# PCB_VHDCI_breakout.net
KiCad netlist of a schematic drawn in Altium Designer
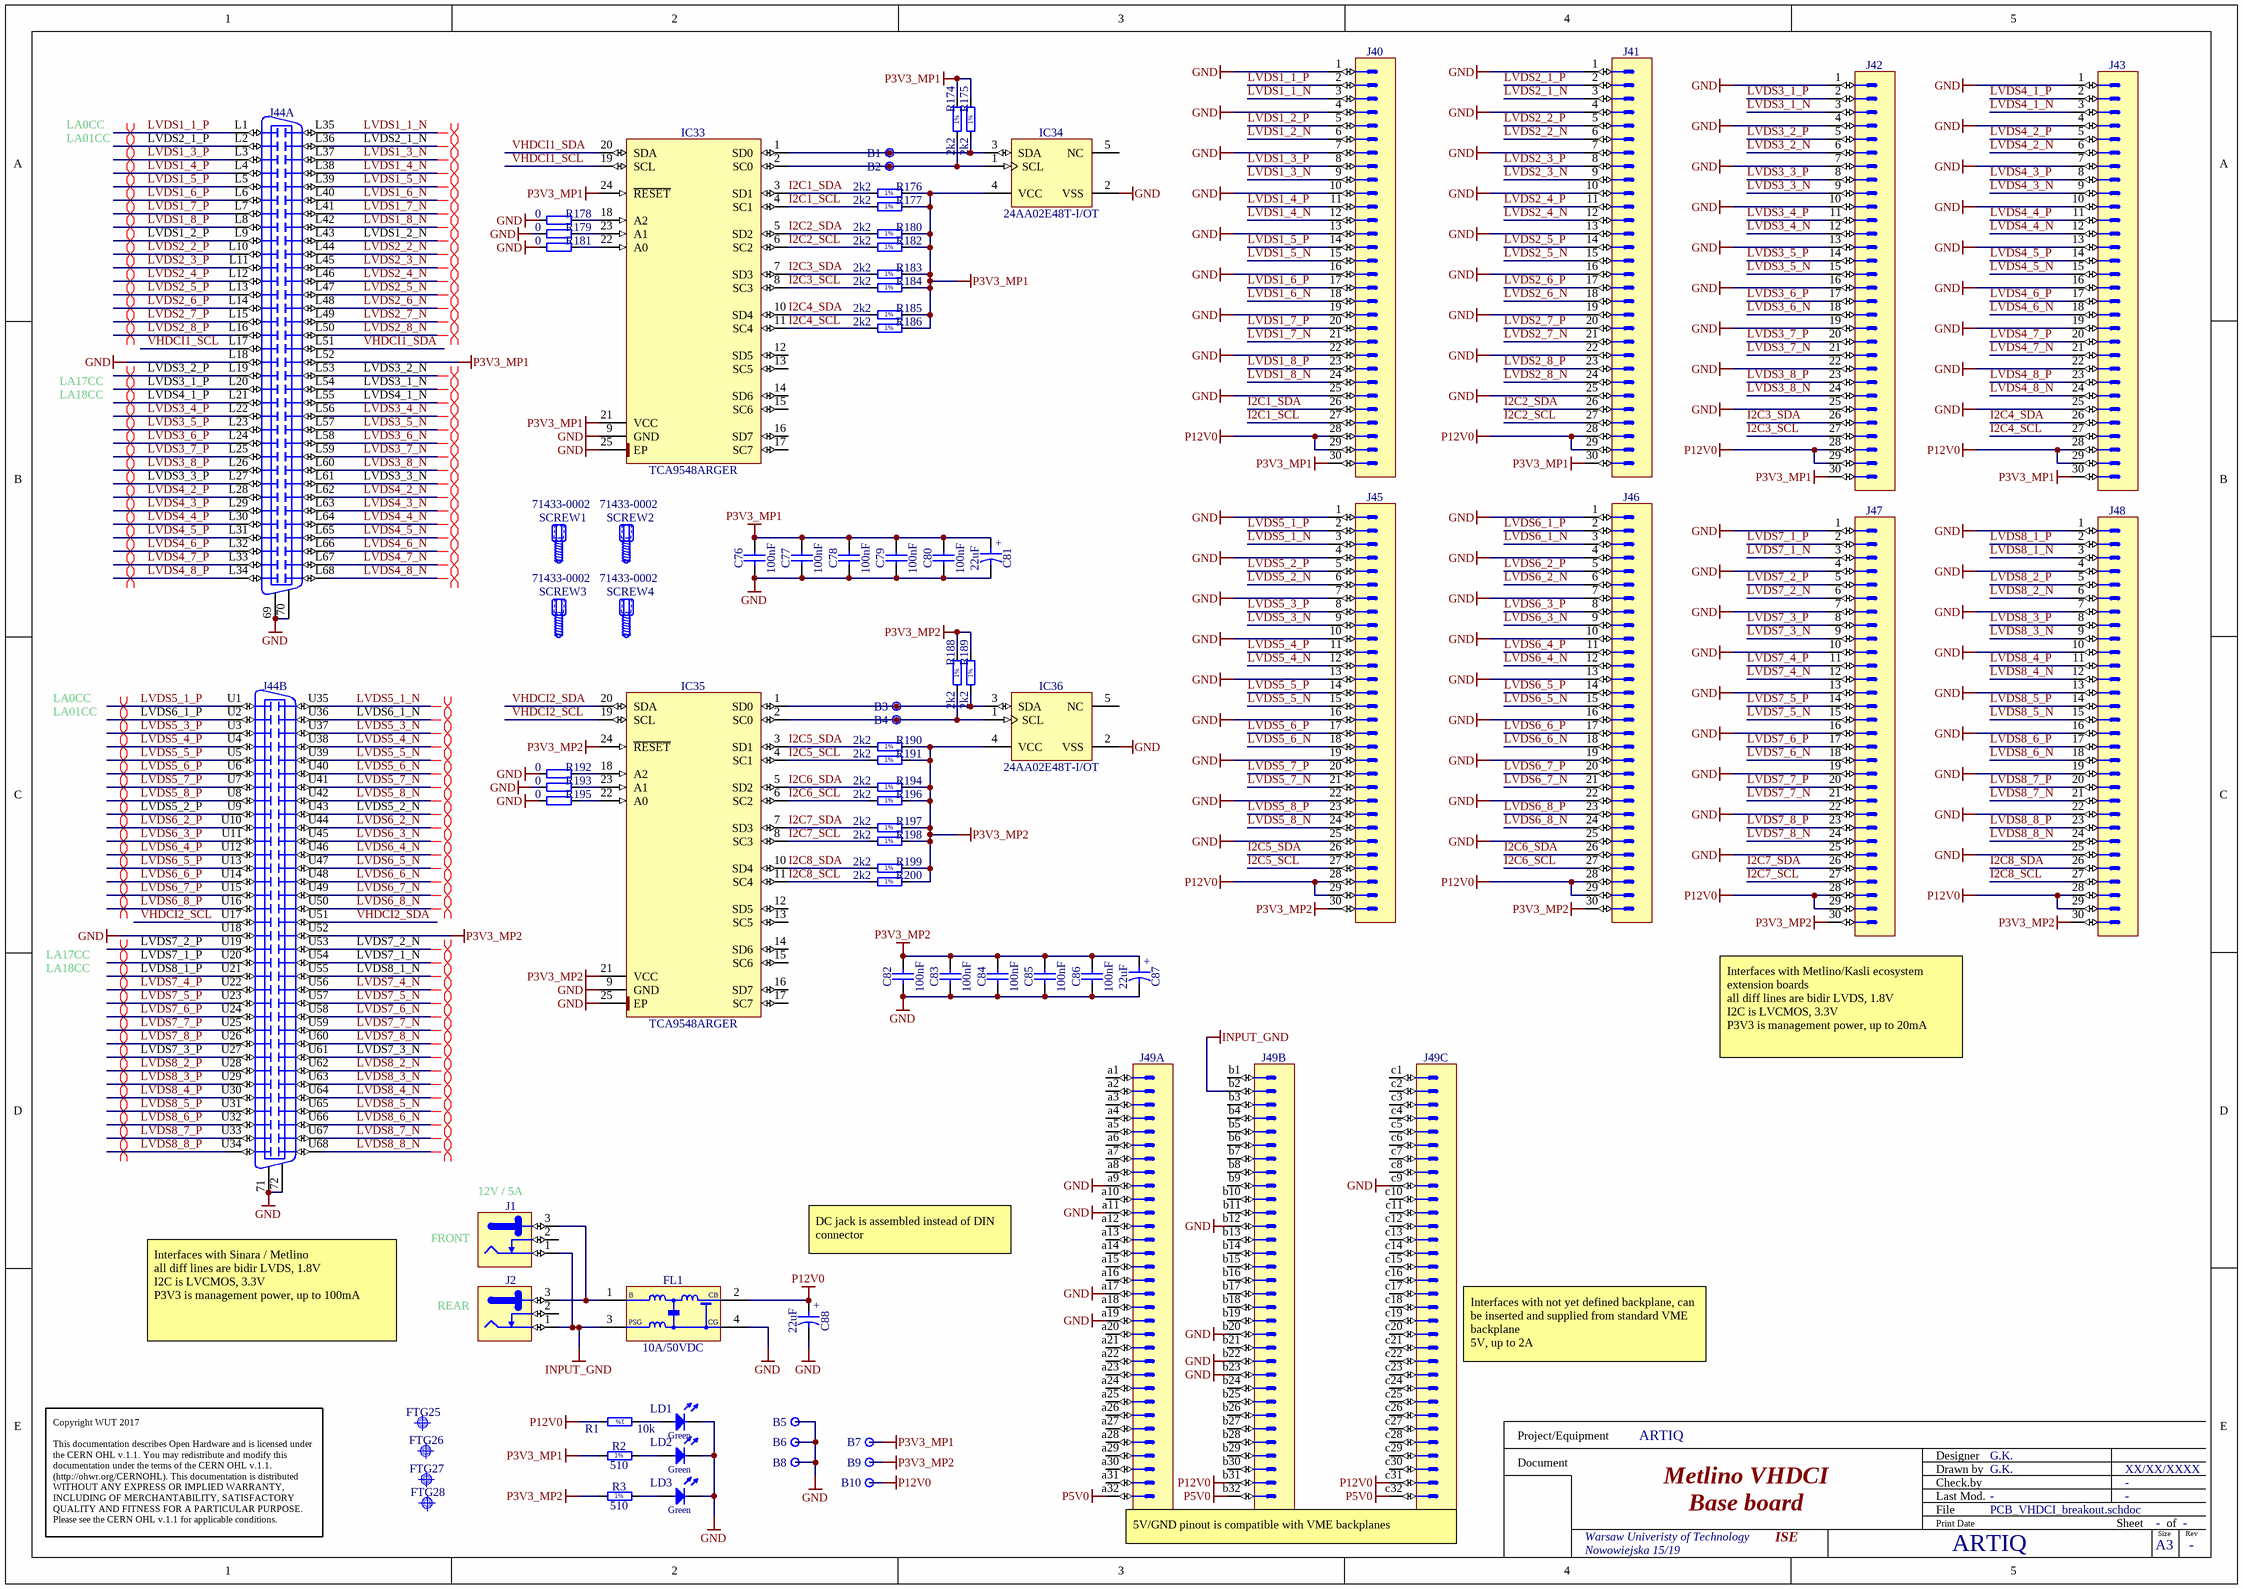
[diagram p0: PCB_VHDCI_breakout.schdoc]

(export (version "E")
  (design (tool "Eeschema 10.0.6"))
  (components
    (comp (ref "B1")
      (value "Plated Hole")
      (footprint "c130h60")
      (description "Single Terminal Socket")
      (fields (field (name "PART NUMBER") "PLATED_HOLE0.6_PAD1.3") (field (name "AUTHOR") "CERN DEM MR"))
      (libsource (lib "Eletro-mechanical") (part "Single Terminal Socket"))
    )
    (comp (ref "B2")
      (value "Plated Hole")
      (footprint "c130h60")
      (description "Single Terminal Socket")
      (fields (field (name "PART NUMBER") "PLATED_HOLE0.6_PAD1.3") (field (name "AUTHOR") "CERN DEM MR"))
      (libsource (lib "Eletro-mechanical") (part "Single Terminal Socket"))
    )
    (comp (ref "B3")
      (value "Plated Hole")
      (footprint "c130h60")
      (description "Single Terminal Socket")
      (fields (field (name "PART NUMBER") "PLATED_HOLE0.6_PAD1.3") (field (name "AUTHOR") "CERN DEM MR"))
      (libsource (lib "Eletro-mechanical") (part "Single Terminal Socket"))
    )
    (comp (ref "B4")
      (value "Plated Hole")
      (footprint "c130h60")
      (description "Single Terminal Socket")
      (fields (field (name "PART NUMBER") "PLATED_HOLE0.6_PAD1.3") (field (name "AUTHOR") "CERN DEM MR"))
      (libsource (lib "Eletro-mechanical") (part "Single Terminal Socket"))
    )
    (comp (ref "B5")
      (value "Plated Hole")
      (footprint "c130h60")
      (description "Single Terminal Socket")
      (fields (field (name "PART NUMBER") "PLATED_HOLE0.6_PAD1.3") (field (name "AUTHOR") "CERN DEM MR"))
      (libsource (lib "Eletro-mechanical") (part "Single Terminal Socket"))
    )
    (comp (ref "B6")
      (value "Plated Hole")
      (footprint "c130h60")
      (description "Single Terminal Socket")
      (fields (field (name "PART NUMBER") "PLATED_HOLE0.6_PAD1.3") (field (name "AUTHOR") "CERN DEM MR"))
      (libsource (lib "Eletro-mechanical") (part "Single Terminal Socket"))
    )
    (comp (ref "B7")
      (value "Plated Hole")
      (footprint "c130h60")
      (description "Single Terminal Socket")
      (fields (field (name "PART NUMBER") "PLATED_HOLE0.6_PAD1.3") (field (name "AUTHOR") "CERN DEM MR"))
      (libsource (lib "Eletro-mechanical") (part "Single Terminal Socket"))
    )
    (comp (ref "B8")
      (value "Plated Hole")
      (footprint "c130h60")
      (description "Single Terminal Socket")
      (fields (field (name "PART NUMBER") "PLATED_HOLE0.6_PAD1.3") (field (name "AUTHOR") "CERN DEM MR"))
      (libsource (lib "Eletro-mechanical") (part "Single Terminal Socket"))
    )
    (comp (ref "B9")
      (value "Plated Hole")
      (footprint "c130h60")
      (description "Single Terminal Socket")
      (fields (field (name "PART NUMBER") "PLATED_HOLE0.6_PAD1.3") (field (name "AUTHOR") "CERN DEM MR"))
      (libsource (lib "Eletro-mechanical") (part "Single Terminal Socket"))
    )
    (comp (ref "B10")
      (value "Plated Hole")
      (footprint "c130h60")
      (description "Single Terminal Socket")
      (fields (field (name "PART NUMBER") "PLATED_HOLE0.6_PAD1.3") (field (name "AUTHOR") "CERN DEM MR"))
      (libsource (lib "Eletro-mechanical") (part "Single Terminal Socket"))
    )
    (comp (ref "C76")
      (value "100nF")
      (footprint "CAPC1005X55N")
      (description "Non-polarised capacitor")
      (fields
        (field (name "PART NUMBER") "CC0402_100NF_16V_10%_X5R")
        (field (name "VOLTAGE") "16V")
        (field (name "AUTHOR") "CERN DEM JLC")
      )
      (libsource (lib "Capacitors") (part "Capacitor - non polarized"))
    )
    (comp (ref "C77")
      (value "100nF")
      (footprint "CAPC1005X55N")
      (description "Non-polarised capacitor")
      (fields
        (field (name "PART NUMBER") "CC0402_100NF_16V_10%_X5R")
        (field (name "VOLTAGE") "16V")
        (field (name "AUTHOR") "CERN DEM JLC")
      )
      (libsource (lib "Capacitors") (part "Capacitor - non polarized"))
    )
    (comp (ref "C78")
      (value "100nF")
      (footprint "CAPC1005X55N")
      (description "Non-polarised capacitor")
      (fields
        (field (name "PART NUMBER") "CC0402_100NF_16V_10%_X5R")
        (field (name "VOLTAGE") "16V")
        (field (name "AUTHOR") "CERN DEM JLC")
      )
      (libsource (lib "Capacitors") (part "Capacitor - non polarized"))
    )
    (comp (ref "C79")
      (value "100nF")
      (footprint "CAPC1005X55N")
      (description "Non-polarised capacitor")
      (fields
        (field (name "PART NUMBER") "CC0402_100NF_16V_10%_X5R")
        (field (name "VOLTAGE") "16V")
        (field (name "AUTHOR") "CERN DEM JLC")
      )
      (libsource (lib "Capacitors") (part "Capacitor - non polarized"))
    )
    (comp (ref "C80")
      (value "100nF")
      (footprint "CAPC1005X55N")
      (description "Non-polarised capacitor")
      (fields
        (field (name "PART NUMBER") "CC0402_100NF_16V_10%_X5R")
        (field (name "VOLTAGE") "16V")
        (field (name "AUTHOR") "CERN DEM JLC")
      )
      (libsource (lib "Capacitors") (part "Capacitor - non polarized"))
    )
    (comp (ref "C81")
      (value "22uF")
      (footprint "CAPAE530X540N")
      (description "Polarised capacitor")
      (fields
        (field (name "PART NUMBER") "CAE530-540_22UF_16V_20%")
        (field (name "VOLTAGE") "16V")
        (field (name "AUTHOR") "CERN DEM JLC")
      )
      (libsource (lib "Capacitors") (part "Capacitor - polarized"))
    )
    (comp (ref "C82")
      (value "100nF")
      (footprint "CAPC1005X55N")
      (description "Non-polarised capacitor")
      (fields
        (field (name "PART NUMBER") "CC0402_100NF_16V_10%_X5R")
        (field (name "VOLTAGE") "16V")
        (field (name "AUTHOR") "CERN DEM JLC")
      )
      (libsource (lib "Capacitors") (part "Capacitor - non polarized"))
    )
    (comp (ref "C83")
      (value "100nF")
      (footprint "CAPC1005X55N")
      (description "Non-polarised capacitor")
      (fields
        (field (name "PART NUMBER") "CC0402_100NF_16V_10%_X5R")
        (field (name "VOLTAGE") "16V")
        (field (name "AUTHOR") "CERN DEM JLC")
      )
      (libsource (lib "Capacitors") (part "Capacitor - non polarized"))
    )
    (comp (ref "C84")
      (value "100nF")
      (footprint "CAPC1005X55N")
      (description "Non-polarised capacitor")
      (fields
        (field (name "PART NUMBER") "CC0402_100NF_16V_10%_X5R")
        (field (name "VOLTAGE") "16V")
        (field (name "AUTHOR") "CERN DEM JLC")
      )
      (libsource (lib "Capacitors") (part "Capacitor - non polarized"))
    )
    (comp (ref "C85")
      (value "100nF")
      (footprint "CAPC1005X55N")
      (description "Non-polarised capacitor")
      (fields
        (field (name "PART NUMBER") "CC0402_100NF_16V_10%_X5R")
        (field (name "VOLTAGE") "16V")
        (field (name "AUTHOR") "CERN DEM JLC")
      )
      (libsource (lib "Capacitors") (part "Capacitor - non polarized"))
    )
    (comp (ref "C86")
      (value "100nF")
      (footprint "CAPC1005X55N")
      (description "Non-polarised capacitor")
      (fields
        (field (name "PART NUMBER") "CC0402_100NF_16V_10%_X5R")
        (field (name "VOLTAGE") "16V")
        (field (name "AUTHOR") "CERN DEM JLC")
      )
      (libsource (lib "Capacitors") (part "Capacitor - non polarized"))
    )
    (comp (ref "C87")
      (value "22uF")
      (footprint "CAPAE530X540N")
      (description "Polarised capacitor")
      (fields
        (field (name "PART NUMBER") "CAE530-540_22UF_16V_20%")
        (field (name "VOLTAGE") "16V")
        (field (name "AUTHOR") "CERN DEM JLC")
      )
      (libsource (lib "Capacitors") (part "Capacitor - polarized"))
    )
    (comp (ref "C88")
      (value "22uF")
      (footprint "CAPAE530X540N")
      (description "Polarised capacitor")
      (fields
        (field (name "PART NUMBER") "CAE530-540_22UF_16V_20%")
        (field (name "VOLTAGE") "16V")
        (field (name "AUTHOR") "CERN DEM JLC")
      )
      (libsource (lib "Capacitors") (part "Capacitor - polarized"))
    )
    (comp (ref "FL1")
      (value "10A/50VDC")
      (footprint "FIL_MURATA_BNX02")
      (description "Block Type EMIFIL (LC Combined)")
      (fields
        (field (name "PART NUMBER") "FIL_MURATA_BNX022-01L")
        (field (name "MANUFACTURER") "MURATA")
        (field (name "AUTHOR") "CERN DEM JLC")
      )
      (libsource (lib "Inductors & Transformers") (part "FIL_MURATA_BNX02"))
    )
    (comp (ref "FTG25")
      (value "Use only in PCB")
      (footprint "FIDUCIAL_TOP_C100-200")
      (description "Fiducial Target")
      (fields (field (name "PART NUMBER") "FIDUCIAL_TARGET_C100-200") (field (name "AUTHOR") "CERN DEM JLC"))
      (libsource (lib "Eletro-mechanical") (part "Fiducial Target"))
    )
    (comp (ref "FTG26")
      (value "Use only in PCB")
      (footprint "FIDUCIAL_TOP_S100-200")
      (description "Fiducial Target")
      (fields (field (name "PART NUMBER") "FIDUCIAL_TARGET_S100-200") (field (name "AUTHOR") "CERN DEM JLC"))
      (libsource (lib "Eletro-mechanical") (part "Fiducial Target"))
    )
    (comp (ref "FTG27")
      (value "Use only in PCB")
      (footprint "FIDUCIAL_TOP_S200-400")
      (description "Fiducial Target")
      (fields (field (name "PART NUMBER") "FIDUCIAL_TARGET_S200-400") (field (name "AUTHOR") "CERN DEM JLC"))
      (libsource (lib "Eletro-mechanical") (part "Fiducial Target"))
    )
    (comp (ref "FTG28")
      (value "Use only in PCB")
      (footprint "FIDUCIAL_TOP_S100-200")
      (description "Fiducial Target")
      (fields (field (name "PART NUMBER") "FIDUCIAL_TARGET_S100-200") (field (name "AUTHOR") "CERN DEM JLC"))
      (libsource (lib "Eletro-mechanical") (part "Fiducial Target"))
    )
    (comp (ref "IC33")
      (value "TCA9548ARGER")
      (footprint "QFN50P400X400X100-25N-S220")
      (description "Low Voltage 8-Channel I2C Switch With Reset")
      (fields (field (name "MANUFACTURER") "TEXAS INSTRUMENTS") (field (name "AUTHOR") "CERN DEM JLC"))
      (libsource (lib "ICs And Semiconductors") (part "TCA9548ARGER"))
    )
    (comp (ref "IC34")
      (value "24AA02E48T-I/OT")
      (footprint "SOT95P280X145-5N")
      (description "1.7V-5.5V, 2K I2C Serial EEPROM With EUI-48 Node Identity")
      (fields (field (name "MANUFACTURER") "MICROCHIP TECHNOLOGY") (field (name "AUTHOR") "CERN DEM MR"))
      (libsource (lib "ICs And Semiconductors") (part "24AA02E48T-I/OT"))
    )
    (comp (ref "IC35")
      (value "TCA9548ARGER")
      (footprint "QFN50P400X400X100-25N-S220")
      (description "Low Voltage 8-Channel I2C Switch With Reset")
      (fields (field (name "MANUFACTURER") "TEXAS INSTRUMENTS") (field (name "AUTHOR") "CERN DEM JLC"))
      (libsource (lib "ICs And Semiconductors") (part "TCA9548ARGER"))
    )
    (comp (ref "IC36")
      (value "24AA02E48T-I/OT")
      (footprint "SOT95P280X145-5N")
      (description "1.7V-5.5V, 2K I2C Serial EEPROM With EUI-48 Node Identity")
      (fields (field (name "MANUFACTURER") "MICROCHIP TECHNOLOGY") (field (name "AUTHOR") "CERN DEM MR"))
      (libsource (lib "ICs And Semiconductors") (part "24AA02E48T-I/OT"))
    )
    (comp (ref "J1")
      (value "Jack")
      (footprint "SWITCHCRAFT_L712RA")
      (description "24V /3. 5A, 2.1mm Diameter Pin, SMD DC Power Supply Connector With  Break Contact")
      (fields
        (field (name "PART NUMBER") "SWITCHCRAFT_L712RA")
        (field (name "MANUFACTURER") "SWITCHCRAFT")
        (field (name "AUTHOR") "GK")
      )
      (libsource (lib "LIBRARY_SCH") (part "CON_DC_5A_THT_RA"))
    )
    (comp (ref "J2")
      (value "Jack")
      (footprint "SWITCHCRAFT_L712RA")
      (description "24V /3. 5A, 2.1mm Diameter Pin, SMD DC Power Supply Connector With  Break Contact")
      (fields
        (field (name "PART NUMBER") "SWITCHCRAFT_L712RA")
        (field (name "MANUFACTURER") "SWITCHCRAFT")
        (field (name "AUTHOR") "GK")
      )
      (libsource (lib "LIBRARY_SCH") (part "CON_DC_5A_THT_RA"))
    )
    (comp (ref "J40")
      (value "~")
      (footprint "3M_N2530-6002RB")
      (description "Connector 30 Male")
      (fields
        (field (name "PART NUMBER") "3M_N2530-6002RB")
        (field (name "MANUFACTURER") "3M")
        (field (name "AUTHOR") "CERN DEM JLC")
      )
      (libsource (lib "Connectors") (part "Connector 30 Male"))
    )
    (comp (ref "J41")
      (value "~")
      (footprint "3M_N2530-6002RB")
      (description "Connector 30 Male")
      (fields
        (field (name "PART NUMBER") "3M_N2530-6002RB")
        (field (name "MANUFACTURER") "3M")
        (field (name "AUTHOR") "CERN DEM JLC")
      )
      (libsource (lib "Connectors") (part "Connector 30 Male"))
    )
    (comp (ref "J42")
      (value "~")
      (footprint "3M_N2530-6002RB")
      (description "Connector 30 Male")
      (fields
        (field (name "PART NUMBER") "3M_N2530-6002RB")
        (field (name "MANUFACTURER") "3M")
        (field (name "AUTHOR") "CERN DEM JLC")
      )
      (libsource (lib "Connectors") (part "Connector 30 Male"))
    )
    (comp (ref "J43")
      (value "~")
      (footprint "3M_N2530-6002RB")
      (description "Connector 30 Male")
      (fields
        (field (name "PART NUMBER") "3M_N2530-6002RB")
        (field (name "MANUFACTURER") "3M")
        (field (name "AUTHOR") "CERN DEM JLC")
      )
      (libsource (lib "Connectors") (part "Connector 30 Male"))
    )
    (comp (ref "J44")
      (value "VHDCI")
      (footprint "MOLEX_74337-0015")
      (description "Very High Density Cable Interconnect (VHDCI ) 2x68 Female")
      (fields
        (field (name "PART NUMBER") "Delivered by GK")
        (field (name "MANUFACTURER") "MOLEX")
        (field (name "AUTHOR") "CERN DEM JLC")
      )
      (libsource (lib "Connectors") (part "Connector VHDCI 2x68 Female"))
    )
    (comp (ref "J45")
      (value "~")
      (footprint "3M_N2530-6002RB")
      (description "Connector 30 Male")
      (fields
        (field (name "PART NUMBER") "3M_N2530-6002RB")
        (field (name "MANUFACTURER") "3M")
        (field (name "AUTHOR") "CERN DEM JLC")
      )
      (libsource (lib "Connectors") (part "Connector 30 Male"))
    )
    (comp (ref "J46")
      (value "~")
      (footprint "3M_N2530-6002RB")
      (description "Connector 30 Male")
      (fields
        (field (name "PART NUMBER") "3M_N2530-6002RB")
        (field (name "MANUFACTURER") "3M")
        (field (name "AUTHOR") "CERN DEM JLC")
      )
      (libsource (lib "Connectors") (part "Connector 30 Male"))
    )
    (comp (ref "J47")
      (value "~")
      (footprint "3M_N2530-6002RB")
      (description "Connector 30 Male")
      (fields
        (field (name "PART NUMBER") "3M_N2530-6002RB")
        (field (name "MANUFACTURER") "3M")
        (field (name "AUTHOR") "CERN DEM JLC")
      )
      (libsource (lib "Connectors") (part "Connector 30 Male"))
    )
    (comp (ref "J48")
      (value "~")
      (footprint "3M_N2530-6002RB")
      (description "Connector 30 Male")
      (fields
        (field (name "PART NUMBER") "3M_N2530-6002RB")
        (field (name "MANUFACTURER") "3M")
        (field (name "AUTHOR") "CERN DEM JLC")
      )
      (libsource (lib "Connectors") (part "Connector 30 Male"))
    )
    (comp (ref "J49")
      (value "DNP")
      (footprint "HARTING_09 03 196 2921")
      (description "Connector 96abc male (3x32)")
      (fields
        (field (name "PART NUMBER") "HARTING_09 03 196 2921")
        (field (name "MANUFACTURER") "HARTING")
        (field (name "AUTHOR") "CERN DEM JLC")
      )
      (libsource (lib "Connectors") (part "Connector 96abc male (3x32)"))
    )
    (comp (ref "LD1")
      (value "Green")
      (footprint "LED_KINGBRIGHT_KPH-1608CGCK")
      (description "LED Green 1C 2A")
      (fields
        (field (name "PART NUMBER") "LED_KINGBRIGHT_KPH-1608CGCK")
        (field (name "MANUFACTURER") "KINGBRIGHT")
        (field (name "AUTHOR") "CERN DEM JLC")
      )
      (libsource (lib "ICs And Semiconductors") (part "LED Green 1C 2A"))
    )
    (comp (ref "LD2")
      (value "Green")
      (footprint "LED_KINGBRIGHT_KPH-1608CGCK")
      (description "LED Green 1C 2A")
      (fields
        (field (name "PART NUMBER") "LED_KINGBRIGHT_KPH-1608CGCK")
        (field (name "MANUFACTURER") "KINGBRIGHT")
        (field (name "AUTHOR") "CERN DEM JLC")
      )
      (libsource (lib "ICs And Semiconductors") (part "LED Green 1C 2A"))
    )
    (comp (ref "LD3")
      (value "Green")
      (footprint "LED_KINGBRIGHT_KPH-1608CGCK")
      (description "LED Green 1C 2A")
      (fields
        (field (name "PART NUMBER") "LED_KINGBRIGHT_KPH-1608CGCK")
        (field (name "MANUFACTURER") "KINGBRIGHT")
        (field (name "AUTHOR") "CERN DEM JLC")
      )
      (libsource (lib "ICs And Semiconductors") (part "LED Green 1C 2A"))
    )
    (comp (ref "R1")
      (value "10k")
      (footprint "RESC1005X40N")
      (description "Resistor - 1%")
      (fields
        (field (name "PART NUMBER") "R0402_10K_1%_0.0625W_100PPM")
        (field (name "POWER") "0.0625W")
        (field (name "AUTHOR") "CERN DEM JLC")
      )
      (libsource (lib "Resistors") (part "Resistor - 1%"))
    )
    (comp (ref "R2")
      (value "510")
      (footprint "RESC1005X40N")
      (description "Resistor - 1%")
      (fields
        (field (name "PART NUMBER") "R0402_510R_1%_0.0625W_100PPM")
        (field (name "POWER") "0.0625W")
        (field (name "AUTHOR") "CERN DEM JLC")
      )
      (libsource (lib "Resistors") (part "Resistor - 1%"))
    )
    (comp (ref "R3")
      (value "510")
      (footprint "RESC1005X40N")
      (description "Resistor - 1%")
      (fields
        (field (name "PART NUMBER") "R0402_510R_1%_0.0625W_100PPM")
        (field (name "POWER") "0.0625W")
        (field (name "AUTHOR") "CERN DEM JLC")
      )
      (libsource (lib "Resistors") (part "Resistor - 1%"))
    )
    (comp (ref "R174")
      (value "2k2")
      (footprint "RESC1005X40N")
      (description "Resistor - 1%")
      (fields
        (field (name "PART NUMBER") "R0402_2K2_1%_0.0625W_100PPM")
        (field (name "POWER") "0.0625W")
        (field (name "AUTHOR") "CERN DEM JLC")
      )
      (libsource (lib "Resistors") (part "Resistor - 1%"))
    )
    (comp (ref "R175")
      (value "2k2")
      (footprint "RESC1005X40N")
      (description "Resistor - 1%")
      (fields
        (field (name "PART NUMBER") "R0402_2K2_1%_0.0625W_100PPM")
        (field (name "POWER") "0.0625W")
        (field (name "AUTHOR") "CERN DEM JLC")
      )
      (libsource (lib "Resistors") (part "Resistor - 1%"))
    )
    (comp (ref "R176")
      (value "2k2")
      (footprint "RESC1005X40N")
      (description "Resistor - 1%")
      (fields
        (field (name "PART NUMBER") "R0402_2K2_1%_0.0625W_100PPM")
        (field (name "POWER") "0.0625W")
        (field (name "AUTHOR") "CERN DEM JLC")
      )
      (libsource (lib "Resistors") (part "Resistor - 1%"))
    )
    (comp (ref "R177")
      (value "2k2")
      (footprint "RESC1005X40N")
      (description "Resistor - 1%")
      (fields
        (field (name "PART NUMBER") "R0402_2K2_1%_0.0625W_100PPM")
        (field (name "POWER") "0.0625W")
        (field (name "AUTHOR") "CERN DEM JLC")
      )
      (libsource (lib "Resistors") (part "Resistor - 1%"))
    )
    (comp (ref "R178")
      (value "0")
      (footprint "RESC1005X40N")
      (description "Resistor")
      (fields
        (field (name "PART NUMBER") "R0402_0R_JUMPER")
        (field (name "MANUFACTURER") "GENERIC")
        (field (name "AUTHOR") "CERN DEM JLC")
      )
      (libsource (lib "Resistors") (part "Resistor"))
    )
    (comp (ref "R179")
      (value "0")
      (footprint "RESC1005X40N")
      (description "Resistor")
      (fields
        (field (name "PART NUMBER") "R0402_0R_JUMPER")
        (field (name "MANUFACTURER") "GENERIC")
        (field (name "AUTHOR") "CERN DEM JLC")
      )
      (libsource (lib "Resistors") (part "Resistor"))
    )
    (comp (ref "R180")
      (value "2k2")
      (footprint "RESC1005X40N")
      (description "Resistor - 1%")
      (fields
        (field (name "PART NUMBER") "R0402_2K2_1%_0.0625W_100PPM")
        (field (name "POWER") "0.0625W")
        (field (name "AUTHOR") "CERN DEM JLC")
      )
      (libsource (lib "Resistors") (part "Resistor - 1%"))
    )
    (comp (ref "R181")
      (value "0")
      (footprint "RESC1005X40N")
      (description "Resistor")
      (fields
        (field (name "PART NUMBER") "R0402_0R_JUMPER")
        (field (name "MANUFACTURER") "GENERIC")
        (field (name "AUTHOR") "CERN DEM JLC")
      )
      (libsource (lib "Resistors") (part "Resistor"))
    )
    (comp (ref "R182")
      (value "2k2")
      (footprint "RESC1005X40N")
      (description "Resistor - 1%")
      (fields
        (field (name "PART NUMBER") "R0402_2K2_1%_0.0625W_100PPM")
        (field (name "POWER") "0.0625W")
        (field (name "AUTHOR") "CERN DEM JLC")
      )
      (libsource (lib "Resistors") (part "Resistor - 1%"))
    )
    (comp (ref "R183")
      (value "2k2")
      (footprint "RESC1005X40N")
      (description "Resistor - 1%")
      (fields
        (field (name "PART NUMBER") "R0402_2K2_1%_0.0625W_100PPM")
        (field (name "POWER") "0.0625W")
        (field (name "AUTHOR") "CERN DEM JLC")
      )
      (libsource (lib "Resistors") (part "Resistor - 1%"))
    )
    (comp (ref "R184")
      (value "2k2")
      (footprint "RESC1005X40N")
      (description "Resistor - 1%")
      (fields
        (field (name "PART NUMBER") "R0402_2K2_1%_0.0625W_100PPM")
        (field (name "POWER") "0.0625W")
        (field (name "AUTHOR") "CERN DEM JLC")
      )
      (libsource (lib "Resistors") (part "Resistor - 1%"))
    )
    (comp (ref "R185")
      (value "2k2")
      (footprint "RESC1005X40N")
      (description "Resistor - 1%")
      (fields
        (field (name "PART NUMBER") "R0402_2K2_1%_0.0625W_100PPM")
        (field (name "POWER") "0.0625W")
        (field (name "AUTHOR") "CERN DEM JLC")
      )
      (libsource (lib "Resistors") (part "Resistor - 1%"))
    )
    (comp (ref "R186")
      (value "2k2")
      (footprint "RESC1005X40N")
      (description "Resistor - 1%")
      (fields
        (field (name "PART NUMBER") "R0402_2K2_1%_0.0625W_100PPM")
        (field (name "POWER") "0.0625W")
        (field (name "AUTHOR") "CERN DEM JLC")
      )
      (libsource (lib "Resistors") (part "Resistor - 1%"))
    )
    (comp (ref "R188")
      (value "2k2")
      (footprint "RESC1005X40N")
      (description "Resistor - 1%")
      (fields
        (field (name "PART NUMBER") "R0402_2K2_1%_0.0625W_100PPM")
        (field (name "POWER") "0.0625W")
        (field (name "AUTHOR") "CERN DEM JLC")
      )
      (libsource (lib "Resistors") (part "Resistor - 1%"))
    )
    (comp (ref "R189")
      (value "2k2")
      (footprint "RESC1005X40N")
      (description "Resistor - 1%")
      (fields
        (field (name "PART NUMBER") "R0402_2K2_1%_0.0625W_100PPM")
        (field (name "POWER") "0.0625W")
        (field (name "AUTHOR") "CERN DEM JLC")
      )
      (libsource (lib "Resistors") (part "Resistor - 1%"))
    )
    (comp (ref "R190")
      (value "2k2")
      (footprint "RESC1005X40N")
      (description "Resistor - 1%")
      (fields
        (field (name "PART NUMBER") "R0402_2K2_1%_0.0625W_100PPM")
        (field (name "POWER") "0.0625W")
        (field (name "AUTHOR") "CERN DEM JLC")
      )
      (libsource (lib "Resistors") (part "Resistor - 1%"))
    )
    (comp (ref "R191")
      (value "2k2")
      (footprint "RESC1005X40N")
      (description "Resistor - 1%")
      (fields
        (field (name "PART NUMBER") "R0402_2K2_1%_0.0625W_100PPM")
        (field (name "POWER") "0.0625W")
        (field (name "AUTHOR") "CERN DEM JLC")
      )
      (libsource (lib "Resistors") (part "Resistor - 1%"))
    )
    (comp (ref "R192")
      (value "0")
      (footprint "RESC1005X40N")
      (description "Resistor")
      (fields
        (field (name "PART NUMBER") "R0402_0R_JUMPER")
        (field (name "MANUFACTURER") "GENERIC")
        (field (name "AUTHOR") "CERN DEM JLC")
      )
      (libsource (lib "Resistors") (part "Resistor"))
    )
    (comp (ref "R193")
      (value "0")
      (footprint "RESC1005X40N")
      (description "Resistor")
      (fields
        (field (name "PART NUMBER") "R0402_0R_JUMPER")
        (field (name "MANUFACTURER") "GENERIC")
        (field (name "AUTHOR") "CERN DEM JLC")
      )
      (libsource (lib "Resistors") (part "Resistor"))
    )
    (comp (ref "R194")
      (value "2k2")
      (footprint "RESC1005X40N")
      (description "Resistor - 1%")
      (fields
        (field (name "PART NUMBER") "R0402_2K2_1%_0.0625W_100PPM")
        (field (name "POWER") "0.0625W")
        (field (name "AUTHOR") "CERN DEM JLC")
      )
      (libsource (lib "Resistors") (part "Resistor - 1%"))
    )
    (comp (ref "R195")
      (value "0")
      (footprint "RESC1005X40N")
      (description "Resistor")
      (fields
        (field (name "PART NUMBER") "R0402_0R_JUMPER")
        (field (name "MANUFACTURER") "GENERIC")
        (field (name "AUTHOR") "CERN DEM JLC")
      )
      (libsource (lib "Resistors") (part "Resistor"))
    )
    (comp (ref "R196")
      (value "2k2")
      (footprint "RESC1005X40N")
      (description "Resistor - 1%")
      (fields
        (field (name "PART NUMBER") "R0402_2K2_1%_0.0625W_100PPM")
        (field (name "POWER") "0.0625W")
        (field (name "AUTHOR") "CERN DEM JLC")
      )
      (libsource (lib "Resistors") (part "Resistor - 1%"))
    )
    (comp (ref "R197")
      (value "2k2")
      (footprint "RESC1005X40N")
      (description "Resistor - 1%")
      (fields
        (field (name "PART NUMBER") "R0402_2K2_1%_0.0625W_100PPM")
        (field (name "POWER") "0.0625W")
        (field (name "AUTHOR") "CERN DEM JLC")
      )
      (libsource (lib "Resistors") (part "Resistor - 1%"))
    )
    (comp (ref "R198")
      (value "2k2")
      (footprint "RESC1005X40N")
      (description "Resistor - 1%")
      (fields
        (field (name "PART NUMBER") "R0402_2K2_1%_0.0625W_100PPM")
        (field (name "POWER") "0.0625W")
        (field (name "AUTHOR") "CERN DEM JLC")
      )
      (libsource (lib "Resistors") (part "Resistor - 1%"))
    )
    (comp (ref "R199")
      (value "2k2")
      (footprint "RESC1005X40N")
      (description "Resistor - 1%")
      (fields
        (field (name "PART NUMBER") "R0402_2K2_1%_0.0625W_100PPM")
        (field (name "POWER") "0.0625W")
        (field (name "AUTHOR") "CERN DEM JLC")
      )
      (libsource (lib "Resistors") (part "Resistor - 1%"))
    )
    (comp (ref "R200")
      (value "2k2")
      (footprint "RESC1005X40N")
      (description "Resistor - 1%")
      (fields
        (field (name "PART NUMBER") "R0402_2K2_1%_0.0625W_100PPM")
        (field (name "POWER") "0.0625W")
        (field (name "AUTHOR") "CERN DEM JLC")
      )
      (libsource (lib "Resistors") (part "Resistor - 1%"))
    )
    (comp (ref "SCREW1")
      (value "71433-0002")
      (footprint "MOLEX_71433-0002")
      (description "VHDCI Female Screw Lock")
      (fields
        (field (name "PART NUMBER") "MOLEX_71433-0002")
        (field (name "MANUFACTURER") "Molex")
        (field (name "AUTHOR") "GK")
      )
      (libsource (lib "LIBRARY_SCH") (part "MECH_VHDCI_screw_lock"))
    )
    (comp (ref "SCREW2")
      (value "71433-0002")
      (footprint "MOLEX_71433-0002")
      (description "VHDCI Female Screw Lock")
      (fields
        (field (name "PART NUMBER") "MOLEX_71433-0002")
        (field (name "MANUFACTURER") "Molex")
        (field (name "AUTHOR") "GK")
      )
      (libsource (lib "LIBRARY_SCH") (part "MECH_VHDCI_screw_lock"))
    )
    (comp (ref "SCREW3")
      (value "71433-0002")
      (footprint "MOLEX_71433-0002")
      (description "VHDCI Female Screw Lock")
      (fields
        (field (name "PART NUMBER") "MOLEX_71433-0002")
        (field (name "MANUFACTURER") "Molex")
        (field (name "AUTHOR") "GK")
      )
      (libsource (lib "LIBRARY_SCH") (part "MECH_VHDCI_screw_lock"))
    )
    (comp (ref "SCREW4")
      (value "71433-0002")
      (footprint "MOLEX_71433-0002")
      (description "VHDCI Female Screw Lock")
      (fields
        (field (name "PART NUMBER") "MOLEX_71433-0002")
        (field (name "MANUFACTURER") "Molex")
        (field (name "AUTHOR") "GK")
      )
      (libsource (lib "LIBRARY_SCH") (part "MECH_VHDCI_screw_lock"))
    )
  )
  (nets
    (net (code "1") (name "/I2C1_SCL") (class "Default")
      (node (ref "IC33") (pin "4") (pinfunction "SC1_4") (pintype "bidirectional"))
      (node (ref "J40") (pin "27") (pinfunction "27_27") (pintype "bidirectional"))
      (node (ref "R177") (pin "1") (pinfunction "1_1") (pintype "passive"))
    )
    (net (code "2") (name "/I2C1_SDA") (class "Default")
      (node (ref "IC33") (pin "3") (pinfunction "SD1_3") (pintype "bidirectional"))
      (node (ref "J40") (pin "26") (pinfunction "26_26") (pintype "bidirectional"))
      (node (ref "R176") (pin "1") (pinfunction "1_1") (pintype "passive"))
    )
    (net (code "3") (name "/I2C2_SCL") (class "Default")
      (node (ref "IC33") (pin "6") (pinfunction "SC2_6") (pintype "bidirectional"))
      (node (ref "J41") (pin "27") (pinfunction "27_27") (pintype "bidirectional"))
      (node (ref "R182") (pin "1") (pinfunction "1_1") (pintype "passive"))
    )
    (net (code "4") (name "/I2C2_SDA") (class "Default")
      (node (ref "IC33") (pin "5") (pinfunction "SD2_5") (pintype "bidirectional"))
      (node (ref "J41") (pin "26") (pinfunction "26_26") (pintype "bidirectional"))
      (node (ref "R180") (pin "1") (pinfunction "1_1") (pintype "passive"))
    )
    (net (code "5") (name "/I2C3_SCL") (class "Default")
      (node (ref "IC33") (pin "8") (pinfunction "SC3_8") (pintype "bidirectional"))
      (node (ref "J42") (pin "27") (pinfunction "27_27") (pintype "bidirectional"))
      (node (ref "R184") (pin "1") (pinfunction "1_1") (pintype "passive"))
    )
    (net (code "6") (name "/I2C3_SDA") (class "Default")
      (node (ref "IC33") (pin "7") (pinfunction "SD3_7") (pintype "bidirectional"))
      (node (ref "J42") (pin "26") (pinfunction "26_26") (pintype "bidirectional"))
      (node (ref "R183") (pin "1") (pinfunction "1_1") (pintype "passive"))
    )
    (net (code "7") (name "/I2C4_SCL") (class "Default")
      (node (ref "IC33") (pin "11") (pinfunction "SC4_11") (pintype "bidirectional"))
      (node (ref "J43") (pin "27") (pinfunction "27_27") (pintype "bidirectional"))
      (node (ref "R186") (pin "1") (pinfunction "1_1") (pintype "passive"))
    )
    (net (code "8") (name "/I2C4_SDA") (class "Default")
      (node (ref "IC33") (pin "10") (pinfunction "SD4_10") (pintype "bidirectional"))
      (node (ref "J43") (pin "26") (pinfunction "26_26") (pintype "bidirectional"))
      (node (ref "R185") (pin "1") (pinfunction "1_1") (pintype "passive"))
    )
    (net (code "9") (name "/I2C5_SCL") (class "Default")
      (node (ref "IC35") (pin "4") (pinfunction "SC1_4") (pintype "bidirectional"))
      (node (ref "J45") (pin "27") (pinfunction "27_27") (pintype "bidirectional"))
      (node (ref "R191") (pin "1") (pinfunction "1_1") (pintype "passive"))
    )
    (net (code "10") (name "/I2C5_SDA") (class "Default")
      (node (ref "IC35") (pin "3") (pinfunction "SD1_3") (pintype "bidirectional"))
      (node (ref "J45") (pin "26") (pinfunction "26_26") (pintype "bidirectional"))
      (node (ref "R190") (pin "1") (pinfunction "1_1") (pintype "passive"))
    )
    (net (code "11") (name "/I2C6_SCL") (class "Default")
      (node (ref "IC35") (pin "6") (pinfunction "SC2_6") (pintype "bidirectional"))
      (node (ref "J46") (pin "27") (pinfunction "27_27") (pintype "bidirectional"))
      (node (ref "R196") (pin "1") (pinfunction "1_1") (pintype "passive"))
    )
    (net (code "12") (name "/I2C6_SDA") (class "Default")
      (node (ref "IC35") (pin "5") (pinfunction "SD2_5") (pintype "bidirectional"))
      (node (ref "J46") (pin "26") (pinfunction "26_26") (pintype "bidirectional"))
      (node (ref "R194") (pin "1") (pinfunction "1_1") (pintype "passive"))
    )
    (net (code "13") (name "/I2C7_SCL") (class "Default")
      (node (ref "IC35") (pin "8") (pinfunction "SC3_8") (pintype "bidirectional"))
      (node (ref "J47") (pin "27") (pinfunction "27_27") (pintype "bidirectional"))
      (node (ref "R198") (pin "1") (pinfunction "1_1") (pintype "passive"))
    )
    (net (code "14") (name "/I2C7_SDA") (class "Default")
      (node (ref "IC35") (pin "7") (pinfunction "SD3_7") (pintype "bidirectional"))
      (node (ref "J47") (pin "26") (pinfunction "26_26") (pintype "bidirectional"))
      (node (ref "R197") (pin "1") (pinfunction "1_1") (pintype "passive"))
    )
    (net (code "15") (name "/I2C8_SCL") (class "Default")
      (node (ref "IC35") (pin "11") (pinfunction "SC4_11") (pintype "bidirectional"))
      (node (ref "J48") (pin "27") (pinfunction "27_27") (pintype "bidirectional"))
      (node (ref "R200") (pin "1") (pinfunction "1_1") (pintype "passive"))
    )
    (net (code "16") (name "/I2C8_SDA") (class "Default")
      (node (ref "IC35") (pin "10") (pinfunction "SD4_10") (pintype "bidirectional"))
      (node (ref "J48") (pin "26") (pinfunction "26_26") (pintype "bidirectional"))
      (node (ref "R199") (pin "1") (pinfunction "1_1") (pintype "passive"))
    )
    (net (code "17") (name "/LVDS1_1_N") (class "Default")
      (node (ref "J40") (pin "3") (pinfunction "3_3") (pintype "bidirectional"))
      (node (ref "J44") (pin "L35") (pinfunction "35_L35") (pintype "bidirectional"))
    )
    (net (code "18") (name "/LVDS1_1_P") (class "Default")
      (node (ref "J40") (pin "2") (pinfunction "2_2") (pintype "bidirectional"))
      (node (ref "J44") (pin "L1") (pinfunction "1_L1") (pintype "bidirectional"))
    )
    (net (code "19") (name "/LVDS1_2_N") (class "Default")
      (node (ref "J40") (pin "6") (pinfunction "6_6") (pintype "bidirectional"))
      (node (ref "J44") (pin "L43") (pinfunction "43_L43") (pintype "bidirectional"))
    )
    (net (code "20") (name "/LVDS1_2_P") (class "Default")
      (node (ref "J40") (pin "5") (pinfunction "5_5") (pintype "bidirectional"))
      (node (ref "J44") (pin "L9") (pinfunction "9_L9") (pintype "bidirectional"))
    )
    (net (code "21") (name "/LVDS1_3_N") (class "Default")
      (node (ref "J40") (pin "9") (pinfunction "9_9") (pintype "bidirectional"))
      (node (ref "J44") (pin "L37") (pinfunction "37_L37") (pintype "bidirectional"))
    )
    (net (code "22") (name "/LVDS1_3_P") (class "Default")
      (node (ref "J40") (pin "8") (pinfunction "8_8") (pintype "bidirectional"))
      (node (ref "J44") (pin "L3") (pinfunction "3_L3") (pintype "bidirectional"))
    )
    (net (code "23") (name "/LVDS1_4_N") (class "Default")
      (node (ref "J40") (pin "12") (pinfunction "12_12") (pintype "bidirectional"))
      (node (ref "J44") (pin "L38") (pinfunction "38_L38") (pintype "bidirectional"))
    )
    (net (code "24") (name "/LVDS1_4_P") (class "Default")
      (node (ref "J40") (pin "11") (pinfunction "11_11") (pintype "bidirectional"))
      (node (ref "J44") (pin "L4") (pinfunction "4_L4") (pintype "bidirectional"))
    )
    (net (code "25") (name "/LVDS1_5_N") (class "Default")
      (node (ref "J40") (pin "15") (pinfunction "15_15") (pintype "bidirectional"))
      (node (ref "J44") (pin "L39") (pinfunction "39_L39") (pintype "bidirectional"))
    )
    (net (code "26") (name "/LVDS1_5_P") (class "Default")
      (node (ref "J40") (pin "14") (pinfunction "14_14") (pintype "bidirectional"))
      (node (ref "J44") (pin "L5") (pinfunction "5_L5") (pintype "bidirectional"))
    )
    (net (code "27") (name "/LVDS1_6_N") (class "Default")
      (node (ref "J40") (pin "18") (pinfunction "18_18") (pintype "bidirectional"))
      (node (ref "J44") (pin "L40") (pinfunction "40_L40") (pintype "bidirectional"))
    )
    (net (code "28") (name "/LVDS1_6_P") (class "Default")
      (node (ref "J40") (pin "17") (pinfunction "17_17") (pintype "bidirectional"))
      (node (ref "J44") (pin "L6") (pinfunction "6_L6") (pintype "bidirectional"))
    )
    (net (code "29") (name "/LVDS1_7_N") (class "Default")
      (node (ref "J40") (pin "21") (pinfunction "21_21") (pintype "bidirectional"))
      (node (ref "J44") (pin "L41") (pinfunction "41_L41") (pintype "bidirectional"))
    )
    (net (code "30") (name "/LVDS1_7_P") (class "Default")
      (node (ref "J40") (pin "20") (pinfunction "20_20") (pintype "bidirectional"))
      (node (ref "J44") (pin "L7") (pinfunction "7_L7") (pintype "bidirectional"))
    )
    (net (code "31") (name "/LVDS1_8_N") (class "Default")
      (node (ref "J40") (pin "24") (pinfunction "24_24") (pintype "bidirectional"))
      (node (ref "J44") (pin "L42") (pinfunction "42_L42") (pintype "bidirectional"))
    )
    (net (code "32") (name "/LVDS1_8_P") (class "Default")
      (node (ref "J40") (pin "23") (pinfunction "23_23") (pintype "bidirectional"))
      (node (ref "J44") (pin "L8") (pinfunction "8_L8") (pintype "bidirectional"))
    )
    (net (code "33") (name "/LVDS2_1_N") (class "Default")
      (node (ref "J41") (pin "3") (pinfunction "3_3") (pintype "bidirectional"))
      (node (ref "J44") (pin "L36") (pinfunction "36_L36") (pintype "bidirectional"))
    )
    (net (code "34") (name "/LVDS2_1_P") (class "Default")
      (node (ref "J41") (pin "2") (pinfunction "2_2") (pintype "bidirectional"))
      (node (ref "J44") (pin "L2") (pinfunction "2_L2") (pintype "bidirectional"))
    )
    (net (code "35") (name "/LVDS2_2_N") (class "Default")
      (node (ref "J41") (pin "6") (pinfunction "6_6") (pintype "bidirectional"))
      (node (ref "J44") (pin "L44") (pinfunction "44_L44") (pintype "bidirectional"))
    )
    (net (code "36") (name "/LVDS2_2_P") (class "Default")
      (node (ref "J41") (pin "5") (pinfunction "5_5") (pintype "bidirectional"))
      (node (ref "J44") (pin "L10") (pinfunction "10_L10") (pintype "bidirectional"))
    )
    (net (code "37") (name "/LVDS2_3_N") (class "Default")
      (node (ref "J41") (pin "9") (pinfunction "9_9") (pintype "bidirectional"))
      (node (ref "J44") (pin "L45") (pinfunction "45_L45") (pintype "bidirectional"))
    )
    (net (code "38") (name "/LVDS2_3_P") (class "Default")
      (node (ref "J41") (pin "8") (pinfunction "8_8") (pintype "bidirectional"))
      (node (ref "J44") (pin "L11") (pinfunction "11_L11") (pintype "bidirectional"))
    )
    (net (code "39") (name "/LVDS2_4_N") (class "Default")
      (node (ref "J41") (pin "12") (pinfunction "12_12") (pintype "bidirectional"))
      (node (ref "J44") (pin "L46") (pinfunction "46_L46") (pintype "bidirectional"))
    )
    (net (code "40") (name "/LVDS2_4_P") (class "Default")
      (node (ref "J41") (pin "11") (pinfunction "11_11") (pintype "bidirectional"))
      (node (ref "J44") (pin "L12") (pinfunction "12_L12") (pintype "bidirectional"))
    )
    (net (code "41") (name "/LVDS2_5_N") (class "Default")
      (node (ref "J41") (pin "15") (pinfunction "15_15") (pintype "bidirectional"))
      (node (ref "J44") (pin "L47") (pinfunction "47_L47") (pintype "bidirectional"))
    )
    (net (code "42") (name "/LVDS2_5_P") (class "Default")
      (node (ref "J41") (pin "14") (pinfunction "14_14") (pintype "bidirectional"))
      (node (ref "J44") (pin "L13") (pinfunction "13_L13") (pintype "bidirectional"))
    )
    (net (code "43") (name "/LVDS2_6_N") (class "Default")
      (node (ref "J41") (pin "18") (pinfunction "18_18") (pintype "bidirectional"))
      (node (ref "J44") (pin "L48") (pinfunction "48_L48") (pintype "bidirectional"))
    )
    (net (code "44") (name "/LVDS2_6_P") (class "Default")
      (node (ref "J41") (pin "17") (pinfunction "17_17") (pintype "bidirectional"))
      (node (ref "J44") (pin "L14") (pinfunction "14_L14") (pintype "bidirectional"))
    )
    (net (code "45") (name "/LVDS2_7_N") (class "Default")
      (node (ref "J41") (pin "21") (pinfunction "21_21") (pintype "bidirectional"))
      (node (ref "J44") (pin "L49") (pinfunction "49_L49") (pintype "bidirectional"))
    )
    (net (code "46") (name "/LVDS2_7_P") (class "Default")
      (node (ref "J41") (pin "20") (pinfunction "20_20") (pintype "bidirectional"))
      (node (ref "J44") (pin "L15") (pinfunction "15_L15") (pintype "bidirectional"))
    )
    (net (code "47") (name "/LVDS2_8_N") (class "Default")
      (node (ref "J41") (pin "24") (pinfunction "24_24") (pintype "bidirectional"))
      (node (ref "J44") (pin "L50") (pinfunction "50_L50") (pintype "bidirectional"))
    )
    (net (code "48") (name "/LVDS2_8_P") (class "Default")
      (node (ref "J41") (pin "23") (pinfunction "23_23") (pintype "bidirectional"))
      (node (ref "J44") (pin "L16") (pinfunction "16_L16") (pintype "bidirectional"))
    )
    (net (code "49") (name "/LVDS3_1_N") (class "Default")
      (node (ref "J42") (pin "3") (pinfunction "3_3") (pintype "bidirectional"))
      (node (ref "J44") (pin "L54") (pinfunction "54_L54") (pintype "bidirectional"))
    )
    (net (code "50") (name "/LVDS3_1_P") (class "Default")
      (node (ref "J42") (pin "2") (pinfunction "2_2") (pintype "bidirectional"))
      (node (ref "J44") (pin "L20") (pinfunction "20_L20") (pintype "bidirectional"))
    )
    (net (code "51") (name "/LVDS3_2_N") (class "Default")
      (node (ref "J42") (pin "6") (pinfunction "6_6") (pintype "bidirectional"))
      (node (ref "J44") (pin "L53") (pinfunction "53_L53") (pintype "bidirectional"))
    )
    (net (code "52") (name "/LVDS3_2_P") (class "Default")
      (node (ref "J42") (pin "5") (pinfunction "5_5") (pintype "bidirectional"))
      (node (ref "J44") (pin "L19") (pinfunction "19_L19") (pintype "bidirectional"))
    )
    (net (code "53") (name "/LVDS3_3_N") (class "Default")
      (node (ref "J42") (pin "9") (pinfunction "9_9") (pintype "bidirectional"))
      (node (ref "J44") (pin "L61") (pinfunction "61_L61") (pintype "bidirectional"))
    )
    (net (code "54") (name "/LVDS3_3_P") (class "Default")
      (node (ref "J42") (pin "8") (pinfunction "8_8") (pintype "bidirectional"))
      (node (ref "J44") (pin "L27") (pinfunction "27_L27") (pintype "bidirectional"))
    )
    (net (code "55") (name "/LVDS3_4_N") (class "Default")
      (node (ref "J42") (pin "12") (pinfunction "12_12") (pintype "bidirectional"))
      (node (ref "J44") (pin "L56") (pinfunction "56_L56") (pintype "bidirectional"))
    )
    (net (code "56") (name "/LVDS3_4_P") (class "Default")
      (node (ref "J42") (pin "11") (pinfunction "11_11") (pintype "bidirectional"))
      (node (ref "J44") (pin "L22") (pinfunction "22_L22") (pintype "bidirectional"))
    )
    (net (code "57") (name "/LVDS3_5_N") (class "Default")
      (node (ref "J42") (pin "15") (pinfunction "15_15") (pintype "bidirectional"))
      (node (ref "J44") (pin "L57") (pinfunction "57_L57") (pintype "bidirectional"))
    )
    (net (code "58") (name "/LVDS3_5_P") (class "Default")
      (node (ref "J42") (pin "14") (pinfunction "14_14") (pintype "bidirectional"))
      (node (ref "J44") (pin "L23") (pinfunction "23_L23") (pintype "bidirectional"))
    )
    (net (code "59") (name "/LVDS3_6_N") (class "Default")
      (node (ref "J42") (pin "18") (pinfunction "18_18") (pintype "bidirectional"))
      (node (ref "J44") (pin "L58") (pinfunction "58_L58") (pintype "bidirectional"))
    )
    (net (code "60") (name "/LVDS3_6_P") (class "Default")
      (node (ref "J42") (pin "17") (pinfunction "17_17") (pintype "bidirectional"))
      (node (ref "J44") (pin "L24") (pinfunction "24_L24") (pintype "bidirectional"))
    )
    (net (code "61") (name "/LVDS3_7_N") (class "Default")
      (node (ref "J42") (pin "21") (pinfunction "21_21") (pintype "bidirectional"))
      (node (ref "J44") (pin "L59") (pinfunction "59_L59") (pintype "bidirectional"))
    )
    (net (code "62") (name "/LVDS3_7_P") (class "Default")
      (node (ref "J42") (pin "20") (pinfunction "20_20") (pintype "bidirectional"))
      (node (ref "J44") (pin "L25") (pinfunction "25_L25") (pintype "bidirectional"))
    )
    (net (code "63") (name "/LVDS3_8_N") (class "Default")
      (node (ref "J42") (pin "24") (pinfunction "24_24") (pintype "bidirectional"))
      (node (ref "J44") (pin "L60") (pinfunction "60_L60") (pintype "bidirectional"))
    )
    (net (code "64") (name "/LVDS3_8_P") (class "Default")
      (node (ref "J42") (pin "23") (pinfunction "23_23") (pintype "bidirectional"))
      (node (ref "J44") (pin "L26") (pinfunction "26_L26") (pintype "bidirectional"))
    )
    (net (code "65") (name "/LVDS4_1_N") (class "Default")
      (node (ref "J43") (pin "3") (pinfunction "3_3") (pintype "bidirectional"))
      (node (ref "J44") (pin "L55") (pinfunction "55_L55") (pintype "bidirectional"))
    )
    (net (code "66") (name "/LVDS4_1_P") (class "Default")
      (node (ref "J43") (pin "2") (pinfunction "2_2") (pintype "bidirectional"))
      (node (ref "J44") (pin "L21") (pinfunction "21_L21") (pintype "bidirectional"))
    )
    (net (code "67") (name "/LVDS4_2_N") (class "Default")
      (node (ref "J43") (pin "6") (pinfunction "6_6") (pintype "bidirectional"))
      (node (ref "J44") (pin "L62") (pinfunction "62_L62") (pintype "bidirectional"))
    )
    (net (code "68") (name "/LVDS4_2_P") (class "Default")
      (node (ref "J43") (pin "5") (pinfunction "5_5") (pintype "bidirectional"))
      (node (ref "J44") (pin "L28") (pinfunction "28_L28") (pintype "bidirectional"))
    )
    (net (code "69") (name "/LVDS4_3_N") (class "Default")
      (node (ref "J43") (pin "9") (pinfunction "9_9") (pintype "bidirectional"))
      (node (ref "J44") (pin "L63") (pinfunction "63_L63") (pintype "bidirectional"))
    )
    (net (code "70") (name "/LVDS4_3_P") (class "Default")
      (node (ref "J43") (pin "8") (pinfunction "8_8") (pintype "bidirectional"))
      (node (ref "J44") (pin "L29") (pinfunction "29_L29") (pintype "bidirectional"))
    )
    (net (code "71") (name "/LVDS4_4_N") (class "Default")
      (node (ref "J43") (pin "12") (pinfunction "12_12") (pintype "bidirectional"))
      (node (ref "J44") (pin "L64") (pinfunction "64_L64") (pintype "bidirectional"))
    )
    (net (code "72") (name "/LVDS4_4_P") (class "Default")
      (node (ref "J43") (pin "11") (pinfunction "11_11") (pintype "bidirectional"))
      (node (ref "J44") (pin "L30") (pinfunction "30_L30") (pintype "bidirectional"))
    )
    (net (code "73") (name "/LVDS4_5_N") (class "Default")
      (node (ref "J43") (pin "15") (pinfunction "15_15") (pintype "bidirectional"))
      (node (ref "J44") (pin "L65") (pinfunction "65_L65") (pintype "bidirectional"))
    )
    (net (code "74") (name "/LVDS4_5_P") (class "Default")
      (node (ref "J43") (pin "14") (pinfunction "14_14") (pintype "bidirectional"))
      (node (ref "J44") (pin "L31") (pinfunction "31_L31") (pintype "bidirectional"))
    )
    (net (code "75") (name "/LVDS4_6_N") (class "Default")
      (node (ref "J43") (pin "18") (pinfunction "18_18") (pintype "bidirectional"))
      (node (ref "J44") (pin "L66") (pinfunction "66_L66") (pintype "bidirectional"))
    )
    (net (code "76") (name "/LVDS4_6_P") (class "Default")
      (node (ref "J43") (pin "17") (pinfunction "17_17") (pintype "bidirectional"))
      (node (ref "J44") (pin "L32") (pinfunction "32_L32") (pintype "bidirectional"))
    )
    (net (code "77") (name "/LVDS4_7_N") (class "Default")
      (node (ref "J43") (pin "21") (pinfunction "21_21") (pintype "bidirectional"))
      (node (ref "J44") (pin "L67") (pinfunction "67_L67") (pintype "bidirectional"))
    )
    (net (code "78") (name "/LVDS4_7_P") (class "Default")
      (node (ref "J43") (pin "20") (pinfunction "20_20") (pintype "bidirectional"))
      (node (ref "J44") (pin "L33") (pinfunction "33_L33") (pintype "bidirectional"))
    )
    (net (code "79") (name "/LVDS4_8_N") (class "Default")
      (node (ref "J43") (pin "24") (pinfunction "24_24") (pintype "bidirectional"))
      (node (ref "J44") (pin "L68") (pinfunction "68_L68") (pintype "bidirectional"))
    )
    (net (code "80") (name "/LVDS4_8_P") (class "Default")
      (node (ref "J43") (pin "23") (pinfunction "23_23") (pintype "bidirectional"))
      (node (ref "J44") (pin "L34") (pinfunction "34_L34") (pintype "bidirectional"))
    )
    (net (code "81") (name "/LVDS5_1_N") (class "Default")
      (node (ref "J44") (pin "U35") (pinfunction "35_U35") (pintype "bidirectional"))
      (node (ref "J45") (pin "3") (pinfunction "3_3") (pintype "bidirectional"))
    )
    (net (code "82") (name "/LVDS5_1_P") (class "Default")
      (node (ref "J44") (pin "U1") (pinfunction "1_U1") (pintype "bidirectional"))
      (node (ref "J45") (pin "2") (pinfunction "2_2") (pintype "bidirectional"))
    )
    (net (code "83") (name "/LVDS5_2_N") (class "Default")
      (node (ref "J44") (pin "U43") (pinfunction "43_U43") (pintype "bidirectional"))
      (node (ref "J45") (pin "6") (pinfunction "6_6") (pintype "bidirectional"))
    )
    (net (code "84") (name "/LVDS5_2_P") (class "Default")
      (node (ref "J44") (pin "U9") (pinfunction "9_U9") (pintype "bidirectional"))
      (node (ref "J45") (pin "5") (pinfunction "5_5") (pintype "bidirectional"))
    )
    (net (code "85") (name "/LVDS5_3_N") (class "Default")
      (node (ref "J44") (pin "U37") (pinfunction "37_U37") (pintype "bidirectional"))
      (node (ref "J45") (pin "9") (pinfunction "9_9") (pintype "bidirectional"))
    )
    (net (code "86") (name "/LVDS5_3_P") (class "Default")
      (node (ref "J44") (pin "U3") (pinfunction "3_U3") (pintype "bidirectional"))
      (node (ref "J45") (pin "8") (pinfunction "8_8") (pintype "bidirectional"))
    )
    (net (code "87") (name "/LVDS5_4_N") (class "Default")
      (node (ref "J44") (pin "U38") (pinfunction "38_U38") (pintype "bidirectional"))
      (node (ref "J45") (pin "12") (pinfunction "12_12") (pintype "bidirectional"))
    )
    (net (code "88") (name "/LVDS5_4_P") (class "Default")
      (node (ref "J44") (pin "U4") (pinfunction "4_U4") (pintype "bidirectional"))
      (node (ref "J45") (pin "11") (pinfunction "11_11") (pintype "bidirectional"))
    )
    (net (code "89") (name "/LVDS5_5_N") (class "Default")
      (node (ref "J44") (pin "U39") (pinfunction "39_U39") (pintype "bidirectional"))
      (node (ref "J45") (pin "15") (pinfunction "15_15") (pintype "bidirectional"))
    )
    (net (code "90") (name "/LVDS5_5_P") (class "Default")
      (node (ref "J44") (pin "U5") (pinfunction "5_U5") (pintype "bidirectional"))
      (node (ref "J45") (pin "14") (pinfunction "14_14") (pintype "bidirectional"))
    )
    (net (code "91") (name "/LVDS5_6_N") (class "Default")
      (node (ref "J44") (pin "U40") (pinfunction "40_U40") (pintype "bidirectional"))
      (node (ref "J45") (pin "18") (pinfunction "18_18") (pintype "bidirectional"))
    )
    (net (code "92") (name "/LVDS5_6_P") (class "Default")
      (node (ref "J44") (pin "U6") (pinfunction "6_U6") (pintype "bidirectional"))
      (node (ref "J45") (pin "17") (pinfunction "17_17") (pintype "bidirectional"))
    )
    (net (code "93") (name "/LVDS5_7_N") (class "Default")
      (node (ref "J44") (pin "U41") (pinfunction "41_U41") (pintype "bidirectional"))
      (node (ref "J45") (pin "21") (pinfunction "21_21") (pintype "bidirectional"))
    )
    (net (code "94") (name "/LVDS5_7_P") (class "Default")
      (node (ref "J44") (pin "U7") (pinfunction "7_U7") (pintype "bidirectional"))
      (node (ref "J45") (pin "20") (pinfunction "20_20") (pintype "bidirectional"))
    )
    (net (code "95") (name "/LVDS5_8_N") (class "Default")
      (node (ref "J44") (pin "U42") (pinfunction "42_U42") (pintype "bidirectional"))
      (node (ref "J45") (pin "24") (pinfunction "24_24") (pintype "bidirectional"))
    )
    (net (code "96") (name "/LVDS5_8_P") (class "Default")
      (node (ref "J44") (pin "U8") (pinfunction "8_U8") (pintype "bidirectional"))
      (node (ref "J45") (pin "23") (pinfunction "23_23") (pintype "bidirectional"))
    )
    (net (code "97") (name "/LVDS6_1_N") (class "Default")
      (node (ref "J44") (pin "U36") (pinfunction "36_U36") (pintype "bidirectional"))
      (node (ref "J46") (pin "3") (pinfunction "3_3") (pintype "bidirectional"))
    )
    (net (code "98") (name "/LVDS6_1_P") (class "Default")
      (node (ref "J44") (pin "U2") (pinfunction "2_U2") (pintype "bidirectional"))
      (node (ref "J46") (pin "2") (pinfunction "2_2") (pintype "bidirectional"))
    )
    (net (code "99") (name "/LVDS6_2_N") (class "Default")
      (node (ref "J44") (pin "U44") (pinfunction "44_U44") (pintype "bidirectional"))
      (node (ref "J46") (pin "6") (pinfunction "6_6") (pintype "bidirectional"))
    )
    (net (code "100") (name "/LVDS6_2_P") (class "Default")
      (node (ref "J44") (pin "U10") (pinfunction "10_U10") (pintype "bidirectional"))
      (node (ref "J46") (pin "5") (pinfunction "5_5") (pintype "bidirectional"))
    )
    (net (code "101") (name "/LVDS6_3_N") (class "Default")
      (node (ref "J44") (pin "U45") (pinfunction "45_U45") (pintype "bidirectional"))
      (node (ref "J46") (pin "9") (pinfunction "9_9") (pintype "bidirectional"))
    )
    (net (code "102") (name "/LVDS6_3_P") (class "Default")
      (node (ref "J44") (pin "U11") (pinfunction "11_U11") (pintype "bidirectional"))
      (node (ref "J46") (pin "8") (pinfunction "8_8") (pintype "bidirectional"))
    )
    (net (code "103") (name "/LVDS6_4_N") (class "Default")
      (node (ref "J44") (pin "U46") (pinfunction "46_U46") (pintype "bidirectional"))
      (node (ref "J46") (pin "12") (pinfunction "12_12") (pintype "bidirectional"))
    )
    (net (code "104") (name "/LVDS6_4_P") (class "Default")
      (node (ref "J44") (pin "U12") (pinfunction "12_U12") (pintype "bidirectional"))
      (node (ref "J46") (pin "11") (pinfunction "11_11") (pintype "bidirectional"))
    )
    (net (code "105") (name "/LVDS6_5_N") (class "Default")
      (node (ref "J44") (pin "U47") (pinfunction "47_U47") (pintype "bidirectional"))
      (node (ref "J46") (pin "15") (pinfunction "15_15") (pintype "bidirectional"))
    )
    (net (code "106") (name "/LVDS6_5_P") (class "Default")
      (node (ref "J44") (pin "U13") (pinfunction "13_U13") (pintype "bidirectional"))
      (node (ref "J46") (pin "14") (pinfunction "14_14") (pintype "bidirectional"))
    )
    (net (code "107") (name "/LVDS6_6_N") (class "Default")
      (node (ref "J44") (pin "U48") (pinfunction "48_U48") (pintype "bidirectional"))
      (node (ref "J46") (pin "18") (pinfunction "18_18") (pintype "bidirectional"))
    )
    (net (code "108") (name "/LVDS6_6_P") (class "Default")
      (node (ref "J44") (pin "U14") (pinfunction "14_U14") (pintype "bidirectional"))
      (node (ref "J46") (pin "17") (pinfunction "17_17") (pintype "bidirectional"))
    )
    (net (code "109") (name "/LVDS6_7_N") (class "Default")
      (node (ref "J44") (pin "U49") (pinfunction "49_U49") (pintype "bidirectional"))
      (node (ref "J46") (pin "21") (pinfunction "21_21") (pintype "bidirectional"))
    )
    (net (code "110") (name "/LVDS6_7_P") (class "Default")
      (node (ref "J44") (pin "U15") (pinfunction "15_U15") (pintype "bidirectional"))
      (node (ref "J46") (pin "20") (pinfunction "20_20") (pintype "bidirectional"))
    )
    (net (code "111") (name "/LVDS6_8_N") (class "Default")
      (node (ref "J44") (pin "U50") (pinfunction "50_U50") (pintype "bidirectional"))
      (node (ref "J46") (pin "24") (pinfunction "24_24") (pintype "bidirectional"))
    )
    (net (code "112") (name "/LVDS6_8_P") (class "Default")
      (node (ref "J44") (pin "U16") (pinfunction "16_U16") (pintype "bidirectional"))
      (node (ref "J46") (pin "23") (pinfunction "23_23") (pintype "bidirectional"))
    )
    (net (code "113") (name "/LVDS7_1_N") (class "Default")
      (node (ref "J44") (pin "U54") (pinfunction "54_U54") (pintype "bidirectional"))
      (node (ref "J47") (pin "3") (pinfunction "3_3") (pintype "bidirectional"))
    )
    (net (code "114") (name "/LVDS7_1_P") (class "Default")
      (node (ref "J44") (pin "U20") (pinfunction "20_U20") (pintype "bidirectional"))
      (node (ref "J47") (pin "2") (pinfunction "2_2") (pintype "bidirectional"))
    )
    (net (code "115") (name "/LVDS7_2_N") (class "Default")
      (node (ref "J44") (pin "U53") (pinfunction "53_U53") (pintype "bidirectional"))
      (node (ref "J47") (pin "6") (pinfunction "6_6") (pintype "bidirectional"))
    )
    (net (code "116") (name "/LVDS7_2_P") (class "Default")
      (node (ref "J44") (pin "U19") (pinfunction "19_U19") (pintype "bidirectional"))
      (node (ref "J47") (pin "5") (pinfunction "5_5") (pintype "bidirectional"))
    )
    (net (code "117") (name "/LVDS7_3_N") (class "Default")
      (node (ref "J44") (pin "U61") (pinfunction "61_U61") (pintype "bidirectional"))
      (node (ref "J47") (pin "9") (pinfunction "9_9") (pintype "bidirectional"))
    )
    (net (code "118") (name "/LVDS7_3_P") (class "Default")
      (node (ref "J44") (pin "U27") (pinfunction "27_U27") (pintype "bidirectional"))
      (node (ref "J47") (pin "8") (pinfunction "8_8") (pintype "bidirectional"))
    )
    (net (code "119") (name "/LVDS7_4_N") (class "Default")
      (node (ref "J44") (pin "U56") (pinfunction "56_U56") (pintype "bidirectional"))
      (node (ref "J47") (pin "12") (pinfunction "12_12") (pintype "bidirectional"))
    )
    (net (code "120") (name "/LVDS7_4_P") (class "Default")
      (node (ref "J44") (pin "U22") (pinfunction "22_U22") (pintype "bidirectional"))
      (node (ref "J47") (pin "11") (pinfunction "11_11") (pintype "bidirectional"))
    )
    (net (code "121") (name "/LVDS7_5_N") (class "Default")
      (node (ref "J44") (pin "U57") (pinfunction "57_U57") (pintype "bidirectional"))
      (node (ref "J47") (pin "15") (pinfunction "15_15") (pintype "bidirectional"))
    )
    (net (code "122") (name "/LVDS7_5_P") (class "Default")
      (node (ref "J44") (pin "U23") (pinfunction "23_U23") (pintype "bidirectional"))
      (node (ref "J47") (pin "14") (pinfunction "14_14") (pintype "bidirectional"))
    )
    (net (code "123") (name "/LVDS7_6_N") (class "Default")
      (node (ref "J44") (pin "U58") (pinfunction "58_U58") (pintype "bidirectional"))
      (node (ref "J47") (pin "18") (pinfunction "18_18") (pintype "bidirectional"))
    )
    (net (code "124") (name "/LVDS7_6_P") (class "Default")
      (node (ref "J44") (pin "U24") (pinfunction "24_U24") (pintype "bidirectional"))
      (node (ref "J47") (pin "17") (pinfunction "17_17") (pintype "bidirectional"))
    )
    (net (code "125") (name "/LVDS7_7_N") (class "Default")
      (node (ref "J44") (pin "U59") (pinfunction "59_U59") (pintype "bidirectional"))
      (node (ref "J47") (pin "21") (pinfunction "21_21") (pintype "bidirectional"))
    )
    (net (code "126") (name "/LVDS7_7_P") (class "Default")
      (node (ref "J44") (pin "U25") (pinfunction "25_U25") (pintype "bidirectional"))
      (node (ref "J47") (pin "20") (pinfunction "20_20") (pintype "bidirectional"))
    )
    (net (code "127") (name "/LVDS7_8_N") (class "Default")
      (node (ref "J44") (pin "U60") (pinfunction "60_U60") (pintype "bidirectional"))
      (node (ref "J47") (pin "24") (pinfunction "24_24") (pintype "bidirectional"))
    )
    (net (code "128") (name "/LVDS7_8_P") (class "Default")
      (node (ref "J44") (pin "U26") (pinfunction "26_U26") (pintype "bidirectional"))
      (node (ref "J47") (pin "23") (pinfunction "23_23") (pintype "bidirectional"))
    )
    (net (code "129") (name "/LVDS8_1_N") (class "Default")
      (node (ref "J44") (pin "U55") (pinfunction "55_U55") (pintype "bidirectional"))
      (node (ref "J48") (pin "3") (pinfunction "3_3") (pintype "bidirectional"))
    )
    (net (code "130") (name "/LVDS8_1_P") (class "Default")
      (node (ref "J44") (pin "U21") (pinfunction "21_U21") (pintype "bidirectional"))
      (node (ref "J48") (pin "2") (pinfunction "2_2") (pintype "bidirectional"))
    )
    (net (code "131") (name "/LVDS8_2_N") (class "Default")
      (node (ref "J44") (pin "U62") (pinfunction "62_U62") (pintype "bidirectional"))
      (node (ref "J48") (pin "6") (pinfunction "6_6") (pintype "bidirectional"))
    )
    (net (code "132") (name "/LVDS8_2_P") (class "Default")
      (node (ref "J44") (pin "U28") (pinfunction "28_U28") (pintype "bidirectional"))
      (node (ref "J48") (pin "5") (pinfunction "5_5") (pintype "bidirectional"))
    )
    (net (code "133") (name "/LVDS8_3_N") (class "Default")
      (node (ref "J44") (pin "U63") (pinfunction "63_U63") (pintype "bidirectional"))
      (node (ref "J48") (pin "9") (pinfunction "9_9") (pintype "bidirectional"))
    )
    (net (code "134") (name "/LVDS8_3_P") (class "Default")
      (node (ref "J44") (pin "U29") (pinfunction "29_U29") (pintype "bidirectional"))
      (node (ref "J48") (pin "8") (pinfunction "8_8") (pintype "bidirectional"))
    )
    (net (code "135") (name "/LVDS8_4_N") (class "Default")
      (node (ref "J44") (pin "U64") (pinfunction "64_U64") (pintype "bidirectional"))
      (node (ref "J48") (pin "12") (pinfunction "12_12") (pintype "bidirectional"))
    )
    (net (code "136") (name "/LVDS8_4_P") (class "Default")
      (node (ref "J44") (pin "U30") (pinfunction "30_U30") (pintype "bidirectional"))
      (node (ref "J48") (pin "11") (pinfunction "11_11") (pintype "bidirectional"))
    )
    (net (code "137") (name "/LVDS8_5_N") (class "Default")
      (node (ref "J44") (pin "U65") (pinfunction "65_U65") (pintype "bidirectional"))
      (node (ref "J48") (pin "15") (pinfunction "15_15") (pintype "bidirectional"))
    )
    (net (code "138") (name "/LVDS8_5_P") (class "Default")
      (node (ref "J44") (pin "U31") (pinfunction "31_U31") (pintype "bidirectional"))
      (node (ref "J48") (pin "14") (pinfunction "14_14") (pintype "bidirectional"))
    )
    (net (code "139") (name "/LVDS8_6_N") (class "Default")
      (node (ref "J44") (pin "U66") (pinfunction "66_U66") (pintype "bidirectional"))
      (node (ref "J48") (pin "18") (pinfunction "18_18") (pintype "bidirectional"))
    )
    (net (code "140") (name "/LVDS8_6_P") (class "Default")
      (node (ref "J44") (pin "U32") (pinfunction "32_U32") (pintype "bidirectional"))
      (node (ref "J48") (pin "17") (pinfunction "17_17") (pintype "bidirectional"))
    )
    (net (code "141") (name "/LVDS8_7_N") (class "Default")
      (node (ref "J44") (pin "U67") (pinfunction "67_U67") (pintype "bidirectional"))
      (node (ref "J48") (pin "21") (pinfunction "21_21") (pintype "bidirectional"))
    )
    (net (code "142") (name "/LVDS8_7_P") (class "Default")
      (node (ref "J44") (pin "U33") (pinfunction "33_U33") (pintype "bidirectional"))
      (node (ref "J48") (pin "20") (pinfunction "20_20") (pintype "bidirectional"))
    )
    (net (code "143") (name "/LVDS8_8_N") (class "Default")
      (node (ref "J44") (pin "U68") (pinfunction "68_U68") (pintype "bidirectional"))
      (node (ref "J48") (pin "24") (pinfunction "24_24") (pintype "bidirectional"))
    )
    (net (code "144") (name "/LVDS8_8_P") (class "Default")
      (node (ref "J44") (pin "U34") (pinfunction "34_U34") (pintype "bidirectional"))
      (node (ref "J48") (pin "23") (pinfunction "23_23") (pintype "bidirectional"))
    )
    (net (code "145") (name "/VHDCI1_SCL") (class "Default")
      (node (ref "IC33") (pin "19") (pinfunction "SCL_19") (pintype "bidirectional"))
      (node (ref "J44") (pin "L17") (pinfunction "17_L17") (pintype "bidirectional"))
    )
    (net (code "146") (name "/VHDCI1_SDA") (class "Default")
      (node (ref "IC33") (pin "20") (pinfunction "SDA_20") (pintype "bidirectional"))
      (node (ref "J44") (pin "L51") (pinfunction "51_L51") (pintype "bidirectional"))
    )
    (net (code "147") (name "/VHDCI2_SCL") (class "Default")
      (node (ref "IC35") (pin "19") (pinfunction "SCL_19") (pintype "bidirectional"))
      (node (ref "J44") (pin "U17") (pinfunction "17_U17") (pintype "bidirectional"))
    )
    (net (code "148") (name "/VHDCI2_SDA") (class "Default")
      (node (ref "IC35") (pin "20") (pinfunction "SDA_20") (pintype "bidirectional"))
      (node (ref "J44") (pin "U51") (pinfunction "51_U51") (pintype "bidirectional"))
    )
    (net (code "149") (name "GND") (class "Default")
      (node (ref "B5") (pin "1") (pinfunction "1_1") (pintype "bidirectional"))
      (node (ref "B6") (pin "1") (pinfunction "1_1") (pintype "bidirectional"))
      (node (ref "B8") (pin "1") (pinfunction "1_1") (pintype "bidirectional"))
      (node (ref "C76") (pin "1") (pinfunction "1_1") (pintype "passive"))
      (node (ref "C77") (pin "1") (pinfunction "1_1") (pintype "passive"))
      (node (ref "C78") (pin "1") (pinfunction "1_1") (pintype "passive"))
      (node (ref "C79") (pin "1") (pinfunction "1_1") (pintype "passive"))
      (node (ref "C80") (pin "1") (pinfunction "1_1") (pintype "passive"))
      (node (ref "C81") (pin "2") (pinfunction "2_2") (pintype "passive"))
      (node (ref "C82") (pin "1") (pinfunction "1_1") (pintype "passive"))
      (node (ref "C83") (pin "1") (pinfunction "1_1") (pintype "passive"))
      (node (ref "C84") (pin "1") (pinfunction "1_1") (pintype "passive"))
      (node (ref "C85") (pin "1") (pinfunction "1_1") (pintype "passive"))
      (node (ref "C86") (pin "1") (pinfunction "1_1") (pintype "passive"))
      (node (ref "C87") (pin "2") (pinfunction "2_2") (pintype "passive"))
      (node (ref "C88") (pin "2") (pinfunction "2_2") (pintype "passive"))
      (node (ref "FL1") (pin "4") (pinfunction "CG_4") (pintype "passive"))
      (node (ref "IC33") (pin "25") (pinfunction "EP_25") (pintype "power_in"))
      (node (ref "IC33") (pin "9") (pinfunction "GND_9") (pintype "power_in"))
      (node (ref "IC34") (pin "2") (pinfunction "VSS_2") (pintype "power_in"))
      (node (ref "IC35") (pin "25") (pinfunction "EP_25") (pintype "power_in"))
      (node (ref "IC35") (pin "9") (pinfunction "GND_9") (pintype "power_in"))
      (node (ref "IC36") (pin "2") (pinfunction "VSS_2") (pintype "power_in"))
      (node (ref "J40") (pin "1") (pinfunction "1_1") (pintype "bidirectional"))
      (node (ref "J40") (pin "10") (pinfunction "10_10") (pintype "bidirectional"))
      (node (ref "J40") (pin "13") (pinfunction "13_13") (pintype "bidirectional"))
      (node (ref "J40") (pin "16") (pinfunction "16_16") (pintype "bidirectional"))
      (node (ref "J40") (pin "19") (pinfunction "19_19") (pintype "bidirectional"))
      (node (ref "J40") (pin "22") (pinfunction "22_22") (pintype "bidirectional"))
      (node (ref "J40") (pin "25") (pinfunction "25_25") (pintype "bidirectional"))
      (node (ref "J40") (pin "4") (pinfunction "4_4") (pintype "bidirectional"))
      (node (ref "J40") (pin "7") (pinfunction "7_7") (pintype "bidirectional"))
      (node (ref "J41") (pin "1") (pinfunction "1_1") (pintype "bidirectional"))
      (node (ref "J41") (pin "10") (pinfunction "10_10") (pintype "bidirectional"))
      (node (ref "J41") (pin "13") (pinfunction "13_13") (pintype "bidirectional"))
      (node (ref "J41") (pin "16") (pinfunction "16_16") (pintype "bidirectional"))
      (node (ref "J41") (pin "19") (pinfunction "19_19") (pintype "bidirectional"))
      (node (ref "J41") (pin "22") (pinfunction "22_22") (pintype "bidirectional"))
      (node (ref "J41") (pin "25") (pinfunction "25_25") (pintype "bidirectional"))
      (node (ref "J41") (pin "4") (pinfunction "4_4") (pintype "bidirectional"))
      (node (ref "J41") (pin "7") (pinfunction "7_7") (pintype "bidirectional"))
      (node (ref "J42") (pin "1") (pinfunction "1_1") (pintype "bidirectional"))
      (node (ref "J42") (pin "10") (pinfunction "10_10") (pintype "bidirectional"))
      (node (ref "J42") (pin "13") (pinfunction "13_13") (pintype "bidirectional"))
      (node (ref "J42") (pin "16") (pinfunction "16_16") (pintype "bidirectional"))
      (node (ref "J42") (pin "19") (pinfunction "19_19") (pintype "bidirectional"))
      (node (ref "J42") (pin "22") (pinfunction "22_22") (pintype "bidirectional"))
      (node (ref "J42") (pin "25") (pinfunction "25_25") (pintype "bidirectional"))
      (node (ref "J42") (pin "4") (pinfunction "4_4") (pintype "bidirectional"))
      (node (ref "J42") (pin "7") (pinfunction "7_7") (pintype "bidirectional"))
      (node (ref "J43") (pin "1") (pinfunction "1_1") (pintype "bidirectional"))
      (node (ref "J43") (pin "10") (pinfunction "10_10") (pintype "bidirectional"))
      (node (ref "J43") (pin "13") (pinfunction "13_13") (pintype "bidirectional"))
      (node (ref "J43") (pin "16") (pinfunction "16_16") (pintype "bidirectional"))
      (node (ref "J43") (pin "19") (pinfunction "19_19") (pintype "bidirectional"))
      (node (ref "J43") (pin "22") (pinfunction "22_22") (pintype "bidirectional"))
      (node (ref "J43") (pin "25") (pinfunction "25_25") (pintype "bidirectional"))
      (node (ref "J43") (pin "4") (pinfunction "4_4") (pintype "bidirectional"))
      (node (ref "J43") (pin "7") (pinfunction "7_7") (pintype "bidirectional"))
      (node (ref "J44") (pin "69") (pinfunction "69_69") (pintype "passive"))
      (node (ref "J44") (pin "70") (pinfunction "70_70") (pintype "passive"))
      (node (ref "J44") (pin "71") (pinfunction "71_71") (pintype "passive"))
      (node (ref "J44") (pin "72") (pinfunction "72_72") (pintype "passive"))
      (node (ref "J44") (pin "L18") (pinfunction "18_L18") (pintype "bidirectional"))
      (node (ref "J44") (pin "U18") (pinfunction "18_U18") (pintype "bidirectional"))
      (node (ref "J45") (pin "1") (pinfunction "1_1") (pintype "bidirectional"))
      (node (ref "J45") (pin "10") (pinfunction "10_10") (pintype "bidirectional"))
      (node (ref "J45") (pin "13") (pinfunction "13_13") (pintype "bidirectional"))
      (node (ref "J45") (pin "16") (pinfunction "16_16") (pintype "bidirectional"))
      (node (ref "J45") (pin "19") (pinfunction "19_19") (pintype "bidirectional"))
      (node (ref "J45") (pin "22") (pinfunction "22_22") (pintype "bidirectional"))
      (node (ref "J45") (pin "25") (pinfunction "25_25") (pintype "bidirectional"))
      (node (ref "J45") (pin "4") (pinfunction "4_4") (pintype "bidirectional"))
      (node (ref "J45") (pin "7") (pinfunction "7_7") (pintype "bidirectional"))
      (node (ref "J46") (pin "1") (pinfunction "1_1") (pintype "bidirectional"))
      (node (ref "J46") (pin "10") (pinfunction "10_10") (pintype "bidirectional"))
      (node (ref "J46") (pin "13") (pinfunction "13_13") (pintype "bidirectional"))
      (node (ref "J46") (pin "16") (pinfunction "16_16") (pintype "bidirectional"))
      (node (ref "J46") (pin "19") (pinfunction "19_19") (pintype "bidirectional"))
      (node (ref "J46") (pin "22") (pinfunction "22_22") (pintype "bidirectional"))
      (node (ref "J46") (pin "25") (pinfunction "25_25") (pintype "bidirectional"))
      (node (ref "J46") (pin "4") (pinfunction "4_4") (pintype "bidirectional"))
      (node (ref "J46") (pin "7") (pinfunction "7_7") (pintype "bidirectional"))
      (node (ref "J47") (pin "1") (pinfunction "1_1") (pintype "bidirectional"))
      (node (ref "J47") (pin "10") (pinfunction "10_10") (pintype "bidirectional"))
      (node (ref "J47") (pin "13") (pinfunction "13_13") (pintype "bidirectional"))
      (node (ref "J47") (pin "16") (pinfunction "16_16") (pintype "bidirectional"))
      (node (ref "J47") (pin "19") (pinfunction "19_19") (pintype "bidirectional"))
      (node (ref "J47") (pin "22") (pinfunction "22_22") (pintype "bidirectional"))
      (node (ref "J47") (pin "25") (pinfunction "25_25") (pintype "bidirectional"))
      (node (ref "J47") (pin "4") (pinfunction "4_4") (pintype "bidirectional"))
      (node (ref "J47") (pin "7") (pinfunction "7_7") (pintype "bidirectional"))
      (node (ref "J48") (pin "1") (pinfunction "1_1") (pintype "bidirectional"))
      (node (ref "J48") (pin "10") (pinfunction "10_10") (pintype "bidirectional"))
      (node (ref "J48") (pin "13") (pinfunction "13_13") (pintype "bidirectional"))
      (node (ref "J48") (pin "16") (pinfunction "16_16") (pintype "bidirectional"))
      (node (ref "J48") (pin "19") (pinfunction "19_19") (pintype "bidirectional"))
      (node (ref "J48") (pin "22") (pinfunction "22_22") (pintype "bidirectional"))
      (node (ref "J48") (pin "25") (pinfunction "25_25") (pintype "bidirectional"))
      (node (ref "J48") (pin "4") (pinfunction "4_4") (pintype "bidirectional"))
      (node (ref "J48") (pin "7") (pinfunction "7_7") (pintype "bidirectional"))
      (node (ref "J49") (pin "a11") (pinfunction "a11_a11") (pintype "bidirectional"))
      (node (ref "J49") (pin "a17") (pinfunction "a17_a17") (pintype "bidirectional"))
      (node (ref "J49") (pin "a19") (pinfunction "a19_a19") (pintype "bidirectional"))
      (node (ref "J49") (pin "a9") (pinfunction "a9_a9") (pintype "bidirectional"))
      (node (ref "J49") (pin "b12") (pinfunction "b12_b12") (pintype "bidirectional"))
      (node (ref "J49") (pin "b20") (pinfunction "b20_b20") (pintype "bidirectional"))
      (node (ref "J49") (pin "b22") (pinfunction "b22_b22") (pintype "bidirectional"))
      (node (ref "J49") (pin "b23") (pinfunction "b23_b23") (pintype "bidirectional"))
      (node (ref "J49") (pin "c9") (pinfunction "c9_c9") (pintype "bidirectional"))
      (node (ref "LD1") (pin "1") (pinfunction "C_1") (pintype "passive"))
      (node (ref "LD2") (pin "1") (pinfunction "C_1") (pintype "passive"))
      (node (ref "LD3") (pin "1") (pinfunction "C_1") (pintype "passive"))
      (node (ref "R178") (pin "1") (pinfunction "1_1") (pintype "passive"))
      (node (ref "R179") (pin "1") (pinfunction "1_1") (pintype "passive"))
      (node (ref "R181") (pin "1") (pinfunction "1_1") (pintype "passive"))
      (node (ref "R192") (pin "1") (pinfunction "1_1") (pintype "passive"))
      (node (ref "R193") (pin "1") (pinfunction "1_1") (pintype "passive"))
      (node (ref "R195") (pin "1") (pinfunction "1_1") (pintype "passive"))
    )
    (net (code "150") (name "INPUT_GND") (class "Default")
      (node (ref "FL1") (pin "3") (pinfunction "PSG_3") (pintype "passive"))
      (node (ref "J1") (pin "1") (pinfunction "1_1") (pintype "bidirectional"))
      (node (ref "J2") (pin "1") (pinfunction "1_1") (pintype "bidirectional"))
      (node (ref "J49") (pin "b2") (pinfunction "b2_b2") (pintype "bidirectional"))
    )
    (net (code "151") (name "Net-(FL1-B)") (class "Default")
      (node (ref "FL1") (pin "1") (pinfunction "B_1") (pintype "passive"))
      (node (ref "J1") (pin "3") (pinfunction "3_3") (pintype "bidirectional"))
      (node (ref "J2") (pin "3") (pinfunction "3_3") (pintype "bidirectional"))
    )
    (net (code "152") (name "Net-(IC33-A0)") (class "Default")
      (node (ref "IC33") (pin "22") (pinfunction "A0_22") (pintype "input"))
      (node (ref "R181") (pin "2") (pinfunction "2_2") (pintype "passive"))
    )
    (net (code "153") (name "Net-(IC33-A1)") (class "Default")
      (node (ref "IC33") (pin "23") (pinfunction "A1_23") (pintype "input"))
      (node (ref "R179") (pin "2") (pinfunction "2_2") (pintype "passive"))
    )
    (net (code "154") (name "Net-(IC33-A2)") (class "Default")
      (node (ref "IC33") (pin "18") (pinfunction "A2_18") (pintype "input"))
      (node (ref "R178") (pin "2") (pinfunction "2_2") (pintype "passive"))
    )
    (net (code "155") (name "Net-(IC33-SC0)") (class "Default")
      (node (ref "B2") (pin "1") (pinfunction "1_1") (pintype "bidirectional"))
      (node (ref "IC33") (pin "2") (pinfunction "SC0_2") (pintype "bidirectional"))
      (node (ref "IC34") (pin "1") (pinfunction "SCL_1") (pintype "input"))
      (node (ref "R174") (pin "1") (pinfunction "1_1") (pintype "passive"))
    )
    (net (code "156") (name "Net-(IC33-SD0)") (class "Default")
      (node (ref "B1") (pin "1") (pinfunction "1_1") (pintype "bidirectional"))
      (node (ref "IC33") (pin "1") (pinfunction "SD0_1") (pintype "bidirectional"))
      (node (ref "IC34") (pin "3") (pinfunction "SDA_3") (pintype "bidirectional"))
      (node (ref "R175") (pin "1") (pinfunction "1_1") (pintype "passive"))
    )
    (net (code "157") (name "Net-(IC35-A0)") (class "Default")
      (node (ref "IC35") (pin "22") (pinfunction "A0_22") (pintype "input"))
      (node (ref "R195") (pin "2") (pinfunction "2_2") (pintype "passive"))
    )
    (net (code "158") (name "Net-(IC35-A1)") (class "Default")
      (node (ref "IC35") (pin "23") (pinfunction "A1_23") (pintype "input"))
      (node (ref "R193") (pin "2") (pinfunction "2_2") (pintype "passive"))
    )
    (net (code "159") (name "Net-(IC35-A2)") (class "Default")
      (node (ref "IC35") (pin "18") (pinfunction "A2_18") (pintype "input"))
      (node (ref "R192") (pin "2") (pinfunction "2_2") (pintype "passive"))
    )
    (net (code "160") (name "Net-(IC35-SC0)") (class "Default")
      (node (ref "B4") (pin "1") (pinfunction "1_1") (pintype "bidirectional"))
      (node (ref "IC35") (pin "2") (pinfunction "SC0_2") (pintype "bidirectional"))
      (node (ref "IC36") (pin "1") (pinfunction "SCL_1") (pintype "input"))
      (node (ref "R188") (pin "1") (pinfunction "1_1") (pintype "passive"))
    )
    (net (code "161") (name "Net-(IC35-SD0)") (class "Default")
      (node (ref "B3") (pin "1") (pinfunction "1_1") (pintype "bidirectional"))
      (node (ref "IC35") (pin "1") (pinfunction "SD0_1") (pintype "bidirectional"))
      (node (ref "IC36") (pin "3") (pinfunction "SDA_3") (pintype "bidirectional"))
      (node (ref "R189") (pin "1") (pinfunction "1_1") (pintype "passive"))
    )
    (net (code "162") (name "Net-(LD1-A)") (class "Default")
      (node (ref "LD1") (pin "2") (pinfunction "A_2") (pintype "passive"))
      (node (ref "R1") (pin "1") (pinfunction "1_1") (pintype "passive"))
    )
    (net (code "163") (name "Net-(LD2-A)") (class "Default")
      (node (ref "LD2") (pin "2") (pinfunction "A_2") (pintype "passive"))
      (node (ref "R2") (pin "2") (pinfunction "2_2") (pintype "passive"))
    )
    (net (code "164") (name "Net-(LD3-A)") (class "Default")
      (node (ref "LD3") (pin "2") (pinfunction "A_2") (pintype "passive"))
      (node (ref "R3") (pin "2") (pinfunction "2_2") (pintype "passive"))
    )
    (net (code "165") (name "P3V3_MP1") (class "Default")
      (node (ref "B7") (pin "1") (pinfunction "1_1") (pintype "bidirectional"))
      (node (ref "C76") (pin "2") (pinfunction "2_2") (pintype "passive"))
      (node (ref "C77") (pin "2") (pinfunction "2_2") (pintype "passive"))
      (node (ref "C78") (pin "2") (pinfunction "2_2") (pintype "passive"))
      (node (ref "C79") (pin "2") (pinfunction "2_2") (pintype "passive"))
      (node (ref "C80") (pin "2") (pinfunction "2_2") (pintype "passive"))
      (node (ref "C81") (pin "1") (pinfunction "1_1") (pintype "passive"))
      (node (ref "IC33") (pin "21") (pinfunction "VCC_21") (pintype "power_in"))
      (node (ref "IC33") (pin "24") (pinfunction "~{RESET}_24") (pintype "input"))
      (node (ref "IC34") (pin "4") (pinfunction "VCC_4") (pintype "power_in"))
      (node (ref "J40") (pin "30") (pinfunction "30_30") (pintype "bidirectional"))
      (node (ref "J41") (pin "30") (pinfunction "30_30") (pintype "bidirectional"))
      (node (ref "J42") (pin "30") (pinfunction "30_30") (pintype "bidirectional"))
      (node (ref "J43") (pin "30") (pinfunction "30_30") (pintype "bidirectional"))
      (node (ref "J44") (pin "L52") (pinfunction "52_L52") (pintype "bidirectional"))
      (node (ref "R174") (pin "2") (pinfunction "2_2") (pintype "passive"))
      (node (ref "R175") (pin "2") (pinfunction "2_2") (pintype "passive"))
      (node (ref "R176") (pin "2") (pinfunction "2_2") (pintype "passive"))
      (node (ref "R177") (pin "2") (pinfunction "2_2") (pintype "passive"))
      (node (ref "R180") (pin "2") (pinfunction "2_2") (pintype "passive"))
      (node (ref "R182") (pin "2") (pinfunction "2_2") (pintype "passive"))
      (node (ref "R183") (pin "2") (pinfunction "2_2") (pintype "passive"))
      (node (ref "R184") (pin "2") (pinfunction "2_2") (pintype "passive"))
      (node (ref "R185") (pin "2") (pinfunction "2_2") (pintype "passive"))
      (node (ref "R186") (pin "2") (pinfunction "2_2") (pintype "passive"))
      (node (ref "R2") (pin "1") (pinfunction "1_1") (pintype "passive"))
    )
    (net (code "166") (name "P3V3_MP2") (class "Default")
      (node (ref "B9") (pin "1") (pinfunction "1_1") (pintype "bidirectional"))
      (node (ref "C82") (pin "2") (pinfunction "2_2") (pintype "passive"))
      (node (ref "C83") (pin "2") (pinfunction "2_2") (pintype "passive"))
      (node (ref "C84") (pin "2") (pinfunction "2_2") (pintype "passive"))
      (node (ref "C85") (pin "2") (pinfunction "2_2") (pintype "passive"))
      (node (ref "C86") (pin "2") (pinfunction "2_2") (pintype "passive"))
      (node (ref "C87") (pin "1") (pinfunction "1_1") (pintype "passive"))
      (node (ref "IC35") (pin "21") (pinfunction "VCC_21") (pintype "power_in"))
      (node (ref "IC35") (pin "24") (pinfunction "~{RESET}_24") (pintype "input"))
      (node (ref "IC36") (pin "4") (pinfunction "VCC_4") (pintype "power_in"))
      (node (ref "J44") (pin "U52") (pinfunction "52_U52") (pintype "bidirectional"))
      (node (ref "J45") (pin "30") (pinfunction "30_30") (pintype "bidirectional"))
      (node (ref "J46") (pin "30") (pinfunction "30_30") (pintype "bidirectional"))
      (node (ref "J47") (pin "30") (pinfunction "30_30") (pintype "bidirectional"))
      (node (ref "J48") (pin "30") (pinfunction "30_30") (pintype "bidirectional"))
      (node (ref "R188") (pin "2") (pinfunction "2_2") (pintype "passive"))
      (node (ref "R189") (pin "2") (pinfunction "2_2") (pintype "passive"))
      (node (ref "R190") (pin "2") (pinfunction "2_2") (pintype "passive"))
      (node (ref "R191") (pin "2") (pinfunction "2_2") (pintype "passive"))
      (node (ref "R194") (pin "2") (pinfunction "2_2") (pintype "passive"))
      (node (ref "R196") (pin "2") (pinfunction "2_2") (pintype "passive"))
      (node (ref "R197") (pin "2") (pinfunction "2_2") (pintype "passive"))
      (node (ref "R198") (pin "2") (pinfunction "2_2") (pintype "passive"))
      (node (ref "R199") (pin "2") (pinfunction "2_2") (pintype "passive"))
      (node (ref "R200") (pin "2") (pinfunction "2_2") (pintype "passive"))
      (node (ref "R3") (pin "1") (pinfunction "1_1") (pintype "passive"))
    )
    (net (code "167") (name "P5V0") (class "Default")
      (node (ref "J49") (pin "a32") (pinfunction "a32_a32") (pintype "bidirectional"))
      (node (ref "J49") (pin "b32") (pinfunction "b32_b32") (pintype "bidirectional"))
      (node (ref "J49") (pin "c32") (pinfunction "c32_c32") (pintype "bidirectional"))
    )
    (net (code "168") (name "P12V0") (class "Default")
      (node (ref "B10") (pin "1") (pinfunction "1_1") (pintype "bidirectional"))
      (node (ref "C88") (pin "1") (pinfunction "1_1") (pintype "passive"))
      (node (ref "FL1") (pin "2") (pinfunction "CB_2") (pintype "passive"))
      (node (ref "J40") (pin "28") (pinfunction "28_28") (pintype "bidirectional"))
      (node (ref "J40") (pin "29") (pinfunction "29_29") (pintype "bidirectional"))
      (node (ref "J41") (pin "28") (pinfunction "28_28") (pintype "bidirectional"))
      (node (ref "J41") (pin "29") (pinfunction "29_29") (pintype "bidirectional"))
      (node (ref "J42") (pin "28") (pinfunction "28_28") (pintype "bidirectional"))
      (node (ref "J42") (pin "29") (pinfunction "29_29") (pintype "bidirectional"))
      (node (ref "J43") (pin "28") (pinfunction "28_28") (pintype "bidirectional"))
      (node (ref "J43") (pin "29") (pinfunction "29_29") (pintype "bidirectional"))
      (node (ref "J45") (pin "28") (pinfunction "28_28") (pintype "bidirectional"))
      (node (ref "J45") (pin "29") (pinfunction "29_29") (pintype "bidirectional"))
      (node (ref "J46") (pin "28") (pinfunction "28_28") (pintype "bidirectional"))
      (node (ref "J46") (pin "29") (pinfunction "29_29") (pintype "bidirectional"))
      (node (ref "J47") (pin "28") (pinfunction "28_28") (pintype "bidirectional"))
      (node (ref "J47") (pin "29") (pinfunction "29_29") (pintype "bidirectional"))
      (node (ref "J48") (pin "28") (pinfunction "28_28") (pintype "bidirectional"))
      (node (ref "J48") (pin "29") (pinfunction "29_29") (pintype "bidirectional"))
      (node (ref "J49") (pin "b31") (pinfunction "b31_b31") (pintype "bidirectional"))
      (node (ref "J49") (pin "c31") (pinfunction "c31_c31") (pintype "bidirectional"))
      (node (ref "R1") (pin "2") (pinfunction "2_2") (pintype "passive"))
    )
    (net (code "169") (name "unconnected-(IC33-SC5-Pad13)") (class "Default")
      (node (ref "IC33") (pin "13") (pinfunction "SC5_13") (pintype "bidirectional"))
    )
    (net (code "170") (name "unconnected-(IC33-SC6-Pad15)") (class "Default")
      (node (ref "IC33") (pin "15") (pinfunction "SC6_15") (pintype "bidirectional"))
    )
    (net (code "171") (name "unconnected-(IC33-SC7-Pad17)") (class "Default")
      (node (ref "IC33") (pin "17") (pinfunction "SC7_17") (pintype "bidirectional"))
    )
    (net (code "172") (name "unconnected-(IC33-SD5-Pad12)") (class "Default")
      (node (ref "IC33") (pin "12") (pinfunction "SD5_12") (pintype "bidirectional"))
    )
    (net (code "173") (name "unconnected-(IC33-SD6-Pad14)") (class "Default")
      (node (ref "IC33") (pin "14") (pinfunction "SD6_14") (pintype "bidirectional"))
    )
    (net (code "174") (name "unconnected-(IC33-SD7-Pad16)") (class "Default")
      (node (ref "IC33") (pin "16") (pinfunction "SD7_16") (pintype "bidirectional"))
    )
    (net (code "175") (name "unconnected-(IC34-NC-Pad5)") (class "Default")
      (node (ref "IC34") (pin "5") (pinfunction "NC_5") (pintype "passive"))
    )
    (net (code "176") (name "unconnected-(IC35-SC5-Pad13)") (class "Default")
      (node (ref "IC35") (pin "13") (pinfunction "SC5_13") (pintype "bidirectional"))
    )
    (net (code "177") (name "unconnected-(IC35-SC6-Pad15)") (class "Default")
      (node (ref "IC35") (pin "15") (pinfunction "SC6_15") (pintype "bidirectional"))
    )
    (net (code "178") (name "unconnected-(IC35-SC7-Pad17)") (class "Default")
      (node (ref "IC35") (pin "17") (pinfunction "SC7_17") (pintype "bidirectional"))
    )
    (net (code "179") (name "unconnected-(IC35-SD5-Pad12)") (class "Default")
      (node (ref "IC35") (pin "12") (pinfunction "SD5_12") (pintype "bidirectional"))
    )
    (net (code "180") (name "unconnected-(IC35-SD6-Pad14)") (class "Default")
      (node (ref "IC35") (pin "14") (pinfunction "SD6_14") (pintype "bidirectional"))
    )
    (net (code "181") (name "unconnected-(IC35-SD7-Pad16)") (class "Default")
      (node (ref "IC35") (pin "16") (pinfunction "SD7_16") (pintype "bidirectional"))
    )
    (net (code "182") (name "unconnected-(IC36-NC-Pad5)") (class "Default")
      (node (ref "IC36") (pin "5") (pinfunction "NC_5") (pintype "passive"))
    )
    (net (code "183") (name "unconnected-(J1-Pad2)") (class "Default")
      (node (ref "J1") (pin "2") (pinfunction "2_2") (pintype "bidirectional"))
    )
    (net (code "184") (name "unconnected-(J2-Pad2)") (class "Default")
      (node (ref "J2") (pin "2") (pinfunction "2_2") (pintype "bidirectional"))
    )
    (net (code "185") (name "unconnected-(J49-Pada1)") (class "Default")
      (node (ref "J49") (pin "a1") (pinfunction "a1_a1") (pintype "bidirectional"))
    )
    (net (code "186") (name "unconnected-(J49-Pada2)") (class "Default")
      (node (ref "J49") (pin "a2") (pinfunction "a2_a2") (pintype "bidirectional"))
    )
    (net (code "187") (name "unconnected-(J49-Pada3)") (class "Default")
      (node (ref "J49") (pin "a3") (pinfunction "a3_a3") (pintype "bidirectional"))
    )
    (net (code "188") (name "unconnected-(J49-Pada4)") (class "Default")
      (node (ref "J49") (pin "a4") (pinfunction "a4_a4") (pintype "bidirectional"))
    )
    (net (code "189") (name "unconnected-(J49-Pada5)") (class "Default")
      (node (ref "J49") (pin "a5") (pinfunction "a5_a5") (pintype "bidirectional"))
    )
    (net (code "190") (name "unconnected-(J49-Pada6)") (class "Default")
      (node (ref "J49") (pin "a6") (pinfunction "a6_a6") (pintype "bidirectional"))
    )
    (net (code "191") (name "unconnected-(J49-Pada7)") (class "Default")
      (node (ref "J49") (pin "a7") (pinfunction "a7_a7") (pintype "bidirectional"))
    )
    (net (code "192") (name "unconnected-(J49-Pada8)") (class "Default")
      (node (ref "J49") (pin "a8") (pinfunction "a8_a8") (pintype "bidirectional"))
    )
    (net (code "193") (name "unconnected-(J49-Pada10)") (class "Default")
      (node (ref "J49") (pin "a10") (pinfunction "a10_a10") (pintype "bidirectional"))
    )
    (net (code "194") (name "unconnected-(J49-Pada12)") (class "Default")
      (node (ref "J49") (pin "a12") (pinfunction "a12_a12") (pintype "bidirectional"))
    )
    (net (code "195") (name "unconnected-(J49-Pada13)") (class "Default")
      (node (ref "J49") (pin "a13") (pinfunction "a13_a13") (pintype "bidirectional"))
    )
    (net (code "196") (name "unconnected-(J49-Pada14)") (class "Default")
      (node (ref "J49") (pin "a14") (pinfunction "a14_a14") (pintype "bidirectional"))
    )
    (net (code "197") (name "unconnected-(J49-Pada15)") (class "Default")
      (node (ref "J49") (pin "a15") (pinfunction "a15_a15") (pintype "bidirectional"))
    )
    (net (code "198") (name "unconnected-(J49-Pada16)") (class "Default")
      (node (ref "J49") (pin "a16") (pinfunction "a16_a16") (pintype "bidirectional"))
    )
    (net (code "199") (name "unconnected-(J49-Pada18)") (class "Default")
      (node (ref "J49") (pin "a18") (pinfunction "a18_a18") (pintype "bidirectional"))
    )
    (net (code "200") (name "unconnected-(J49-Pada20)") (class "Default")
      (node (ref "J49") (pin "a20") (pinfunction "a20_a20") (pintype "bidirectional"))
    )
    (net (code "201") (name "unconnected-(J49-Pada21)") (class "Default")
      (node (ref "J49") (pin "a21") (pinfunction "a21_a21") (pintype "bidirectional"))
    )
    (net (code "202") (name "unconnected-(J49-Pada22)") (class "Default")
      (node (ref "J49") (pin "a22") (pinfunction "a22_a22") (pintype "bidirectional"))
    )
    (net (code "203") (name "unconnected-(J49-Pada23)") (class "Default")
      (node (ref "J49") (pin "a23") (pinfunction "a23_a23") (pintype "bidirectional"))
    )
    (net (code "204") (name "unconnected-(J49-Pada24)") (class "Default")
      (node (ref "J49") (pin "a24") (pinfunction "a24_a24") (pintype "bidirectional"))
    )
    (net (code "205") (name "unconnected-(J49-Pada25)") (class "Default")
      (node (ref "J49") (pin "a25") (pinfunction "a25_a25") (pintype "bidirectional"))
    )
    (net (code "206") (name "unconnected-(J49-Pada26)") (class "Default")
      (node (ref "J49") (pin "a26") (pinfunction "a26_a26") (pintype "bidirectional"))
    )
    (net (code "207") (name "unconnected-(J49-Pada27)") (class "Default")
      (node (ref "J49") (pin "a27") (pinfunction "a27_a27") (pintype "bidirectional"))
    )
    (net (code "208") (name "unconnected-(J49-Pada28)") (class "Default")
      (node (ref "J49") (pin "a28") (pinfunction "a28_a28") (pintype "bidirectional"))
    )
    (net (code "209") (name "unconnected-(J49-Pada29)") (class "Default")
      (node (ref "J49") (pin "a29") (pinfunction "a29_a29") (pintype "bidirectional"))
    )
    (net (code "210") (name "unconnected-(J49-Pada30)") (class "Default")
      (node (ref "J49") (pin "a30") (pinfunction "a30_a30") (pintype "bidirectional"))
    )
    (net (code "211") (name "unconnected-(J49-Pada31)") (class "Default")
      (node (ref "J49") (pin "a31") (pinfunction "a31_a31") (pintype "bidirectional"))
    )
    (net (code "212") (name "unconnected-(J49-Padb1)") (class "Default")
      (node (ref "J49") (pin "b1") (pinfunction "b1_b1") (pintype "bidirectional"))
    )
    (net (code "213") (name "unconnected-(J49-Padb3)") (class "Default")
      (node (ref "J49") (pin "b3") (pinfunction "b3_b3") (pintype "bidirectional"))
    )
    (net (code "214") (name "unconnected-(J49-Padb4)") (class "Default")
      (node (ref "J49") (pin "b4") (pinfunction "b4_b4") (pintype "bidirectional"))
    )
    (net (code "215") (name "unconnected-(J49-Padb5)") (class "Default")
      (node (ref "J49") (pin "b5") (pinfunction "b5_b5") (pintype "bidirectional"))
    )
    (net (code "216") (name "unconnected-(J49-Padb6)") (class "Default")
      (node (ref "J49") (pin "b6") (pinfunction "b6_b6") (pintype "bidirectional"))
    )
    (net (code "217") (name "unconnected-(J49-Padb7)") (class "Default")
      (node (ref "J49") (pin "b7") (pinfunction "b7_b7") (pintype "bidirectional"))
    )
    (net (code "218") (name "unconnected-(J49-Padb8)") (class "Default")
      (node (ref "J49") (pin "b8") (pinfunction "b8_b8") (pintype "bidirectional"))
    )
    (net (code "219") (name "unconnected-(J49-Padb9)") (class "Default")
      (node (ref "J49") (pin "b9") (pinfunction "b9_b9") (pintype "bidirectional"))
    )
    (net (code "220") (name "unconnected-(J49-Padb10)") (class "Default")
      (node (ref "J49") (pin "b10") (pinfunction "b10_b10") (pintype "bidirectional"))
    )
    (net (code "221") (name "unconnected-(J49-Padb11)") (class "Default")
      (node (ref "J49") (pin "b11") (pinfunction "b11_b11") (pintype "bidirectional"))
    )
    (net (code "222") (name "unconnected-(J49-Padb13)") (class "Default")
      (node (ref "J49") (pin "b13") (pinfunction "b13_b13") (pintype "bidirectional"))
    )
    (net (code "223") (name "unconnected-(J49-Padb14)") (class "Default")
      (node (ref "J49") (pin "b14") (pinfunction "b14_b14") (pintype "bidirectional"))
    )
    (net (code "224") (name "unconnected-(J49-Padb15)") (class "Default")
      (node (ref "J49") (pin "b15") (pinfunction "b15_b15") (pintype "bidirectional"))
    )
    (net (code "225") (name "unconnected-(J49-Padb16)") (class "Default")
      (node (ref "J49") (pin "b16") (pinfunction "b16_b16") (pintype "bidirectional"))
    )
    (net (code "226") (name "unconnected-(J49-Padb17)") (class "Default")
      (node (ref "J49") (pin "b17") (pinfunction "b17_b17") (pintype "bidirectional"))
    )
    (net (code "227") (name "unconnected-(J49-Padb18)") (class "Default")
      (node (ref "J49") (pin "b18") (pinfunction "b18_b18") (pintype "bidirectional"))
    )
    (net (code "228") (name "unconnected-(J49-Padb19)") (class "Default")
      (node (ref "J49") (pin "b19") (pinfunction "b19_b19") (pintype "bidirectional"))
    )
    (net (code "229") (name "unconnected-(J49-Padb21)") (class "Default")
      (node (ref "J49") (pin "b21") (pinfunction "b21_b21") (pintype "bidirectional"))
    )
    (net (code "230") (name "unconnected-(J49-Padb24)") (class "Default")
      (node (ref "J49") (pin "b24") (pinfunction "b24_b24") (pintype "bidirectional"))
    )
    (net (code "231") (name "unconnected-(J49-Padb25)") (class "Default")
      (node (ref "J49") (pin "b25") (pinfunction "b25_b25") (pintype "bidirectional"))
    )
    (net (code "232") (name "unconnected-(J49-Padb26)") (class "Default")
      (node (ref "J49") (pin "b26") (pinfunction "b26_b26") (pintype "bidirectional"))
    )
    (net (code "233") (name "unconnected-(J49-Padb27)") (class "Default")
      (node (ref "J49") (pin "b27") (pinfunction "b27_b27") (pintype "bidirectional"))
    )
    (net (code "234") (name "unconnected-(J49-Padb28)") (class "Default")
      (node (ref "J49") (pin "b28") (pinfunction "b28_b28") (pintype "bidirectional"))
    )
    (net (code "235") (name "unconnected-(J49-Padb29)") (class "Default")
      (node (ref "J49") (pin "b29") (pinfunction "b29_b29") (pintype "bidirectional"))
    )
    (net (code "236") (name "unconnected-(J49-Padb30)") (class "Default")
      (node (ref "J49") (pin "b30") (pinfunction "b30_b30") (pintype "bidirectional"))
    )
    (net (code "237") (name "unconnected-(J49-Padc1)") (class "Default")
      (node (ref "J49") (pin "c1") (pinfunction "c1_c1") (pintype "bidirectional"))
    )
    (net (code "238") (name "unconnected-(J49-Padc2)") (class "Default")
      (node (ref "J49") (pin "c2") (pinfunction "c2_c2") (pintype "bidirectional"))
    )
    (net (code "239") (name "unconnected-(J49-Padc3)") (class "Default")
      (node (ref "J49") (pin "c3") (pinfunction "c3_c3") (pintype "bidirectional"))
    )
    (net (code "240") (name "unconnected-(J49-Padc4)") (class "Default")
      (node (ref "J49") (pin "c4") (pinfunction "c4_c4") (pintype "bidirectional"))
    )
    (net (code "241") (name "unconnected-(J49-Padc5)") (class "Default")
      (node (ref "J49") (pin "c5") (pinfunction "c5_c5") (pintype "bidirectional"))
    )
    (net (code "242") (name "unconnected-(J49-Padc6)") (class "Default")
      (node (ref "J49") (pin "c6") (pinfunction "c6_c6") (pintype "bidirectional"))
    )
    (net (code "243") (name "unconnected-(J49-Padc7)") (class "Default")
      (node (ref "J49") (pin "c7") (pinfunction "c7_c7") (pintype "bidirectional"))
    )
    (net (code "244") (name "unconnected-(J49-Padc8)") (class "Default")
      (node (ref "J49") (pin "c8") (pinfunction "c8_c8") (pintype "bidirectional"))
    )
    (net (code "245") (name "unconnected-(J49-Padc10)") (class "Default")
      (node (ref "J49") (pin "c10") (pinfunction "c10_c10") (pintype "bidirectional"))
    )
    (net (code "246") (name "unconnected-(J49-Padc11)") (class "Default")
      (node (ref "J49") (pin "c11") (pinfunction "c11_c11") (pintype "bidirectional"))
    )
    (net (code "247") (name "unconnected-(J49-Padc12)") (class "Default")
      (node (ref "J49") (pin "c12") (pinfunction "c12_c12") (pintype "bidirectional"))
    )
    (net (code "248") (name "unconnected-(J49-Padc13)") (class "Default")
      (node (ref "J49") (pin "c13") (pinfunction "c13_c13") (pintype "bidirectional"))
    )
    (net (code "249") (name "unconnected-(J49-Padc14)") (class "Default")
      (node (ref "J49") (pin "c14") (pinfunction "c14_c14") (pintype "bidirectional"))
    )
    (net (code "250") (name "unconnected-(J49-Padc15)") (class "Default")
      (node (ref "J49") (pin "c15") (pinfunction "c15_c15") (pintype "bidirectional"))
    )
    (net (code "251") (name "unconnected-(J49-Padc16)") (class "Default")
      (node (ref "J49") (pin "c16") (pinfunction "c16_c16") (pintype "bidirectional"))
    )
    (net (code "252") (name "unconnected-(J49-Padc17)") (class "Default")
      (node (ref "J49") (pin "c17") (pinfunction "c17_c17") (pintype "bidirectional"))
    )
    (net (code "253") (name "unconnected-(J49-Padc18)") (class "Default")
      (node (ref "J49") (pin "c18") (pinfunction "c18_c18") (pintype "bidirectional"))
    )
    (net (code "254") (name "unconnected-(J49-Padc19)") (class "Default")
      (node (ref "J49") (pin "c19") (pinfunction "c19_c19") (pintype "bidirectional"))
    )
    (net (code "255") (name "unconnected-(J49-Padc20)") (class "Default")
      (node (ref "J49") (pin "c20") (pinfunction "c20_c20") (pintype "bidirectional"))
    )
    (net (code "256") (name "unconnected-(J49-Padc21)") (class "Default")
      (node (ref "J49") (pin "c21") (pinfunction "c21_c21") (pintype "bidirectional"))
    )
    (net (code "257") (name "unconnected-(J49-Padc22)") (class "Default")
      (node (ref "J49") (pin "c22") (pinfunction "c22_c22") (pintype "bidirectional"))
    )
    (net (code "258") (name "unconnected-(J49-Padc23)") (class "Default")
      (node (ref "J49") (pin "c23") (pinfunction "c23_c23") (pintype "bidirectional"))
    )
    (net (code "259") (name "unconnected-(J49-Padc24)") (class "Default")
      (node (ref "J49") (pin "c24") (pinfunction "c24_c24") (pintype "bidirectional"))
    )
    (net (code "260") (name "unconnected-(J49-Padc25)") (class "Default")
      (node (ref "J49") (pin "c25") (pinfunction "c25_c25") (pintype "bidirectional"))
    )
    (net (code "261") (name "unconnected-(J49-Padc26)") (class "Default")
      (node (ref "J49") (pin "c26") (pinfunction "c26_c26") (pintype "bidirectional"))
    )
    (net (code "262") (name "unconnected-(J49-Padc27)") (class "Default")
      (node (ref "J49") (pin "c27") (pinfunction "c27_c27") (pintype "bidirectional"))
    )
    (net (code "263") (name "unconnected-(J49-Padc28)") (class "Default")
      (node (ref "J49") (pin "c28") (pinfunction "c28_c28") (pintype "bidirectional"))
    )
    (net (code "264") (name "unconnected-(J49-Padc29)") (class "Default")
      (node (ref "J49") (pin "c29") (pinfunction "c29_c29") (pintype "bidirectional"))
    )
    (net (code "265") (name "unconnected-(J49-Padc30)") (class "Default")
      (node (ref "J49") (pin "c30") (pinfunction "c30_c30") (pintype "bidirectional"))
    )
  )
)
